# Sheet1.net
KiCad netlist of a schematic drawn in Altium Designer
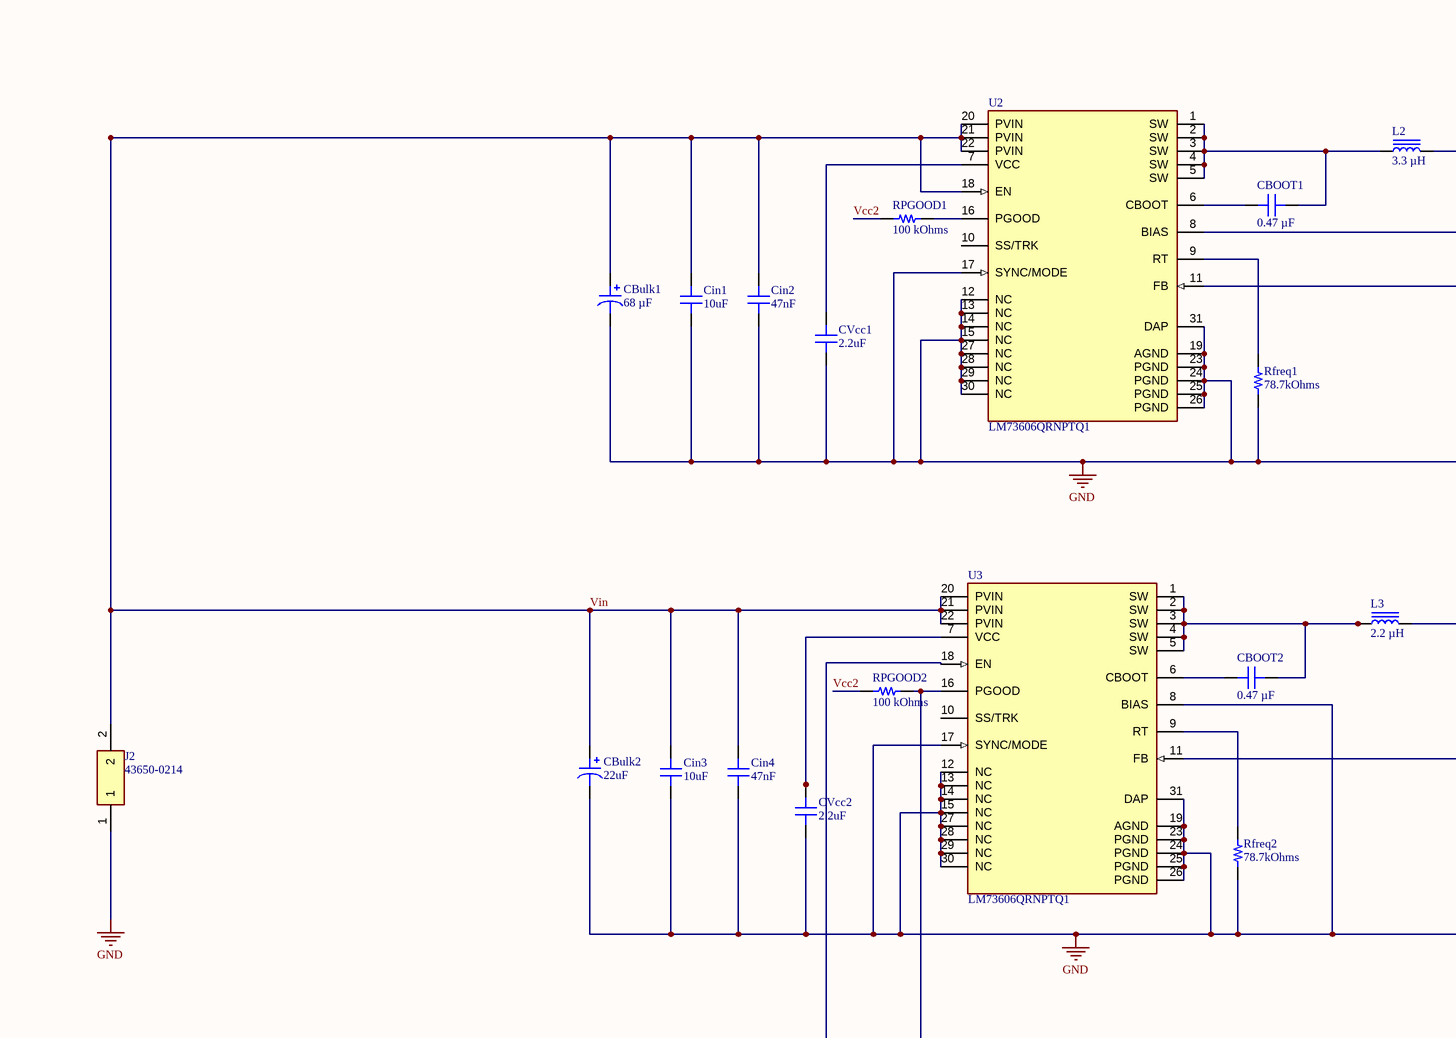
[diagram p0: Sheet1.SchDoc, top left]
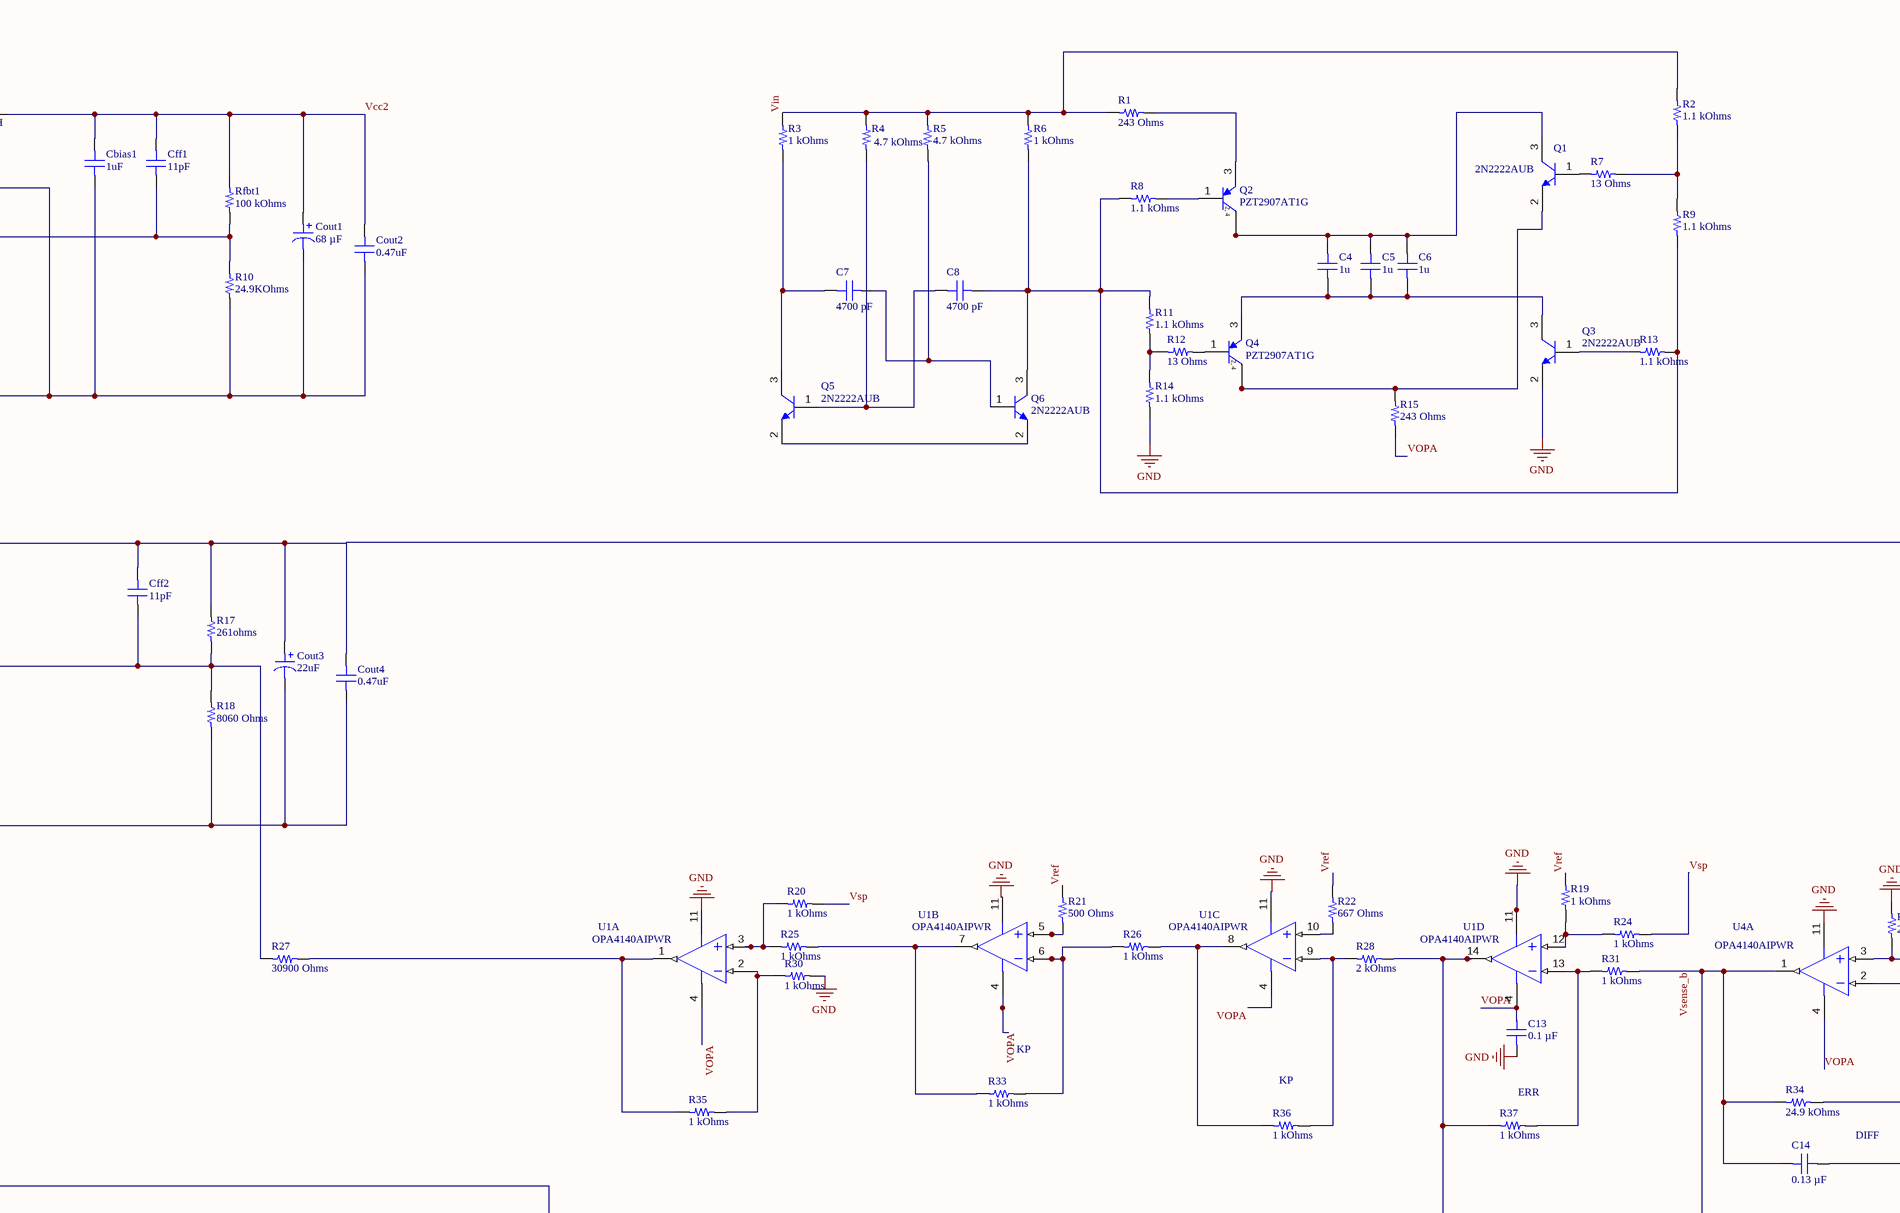
[diagram p1: Sheet1.SchDoc, top middle]
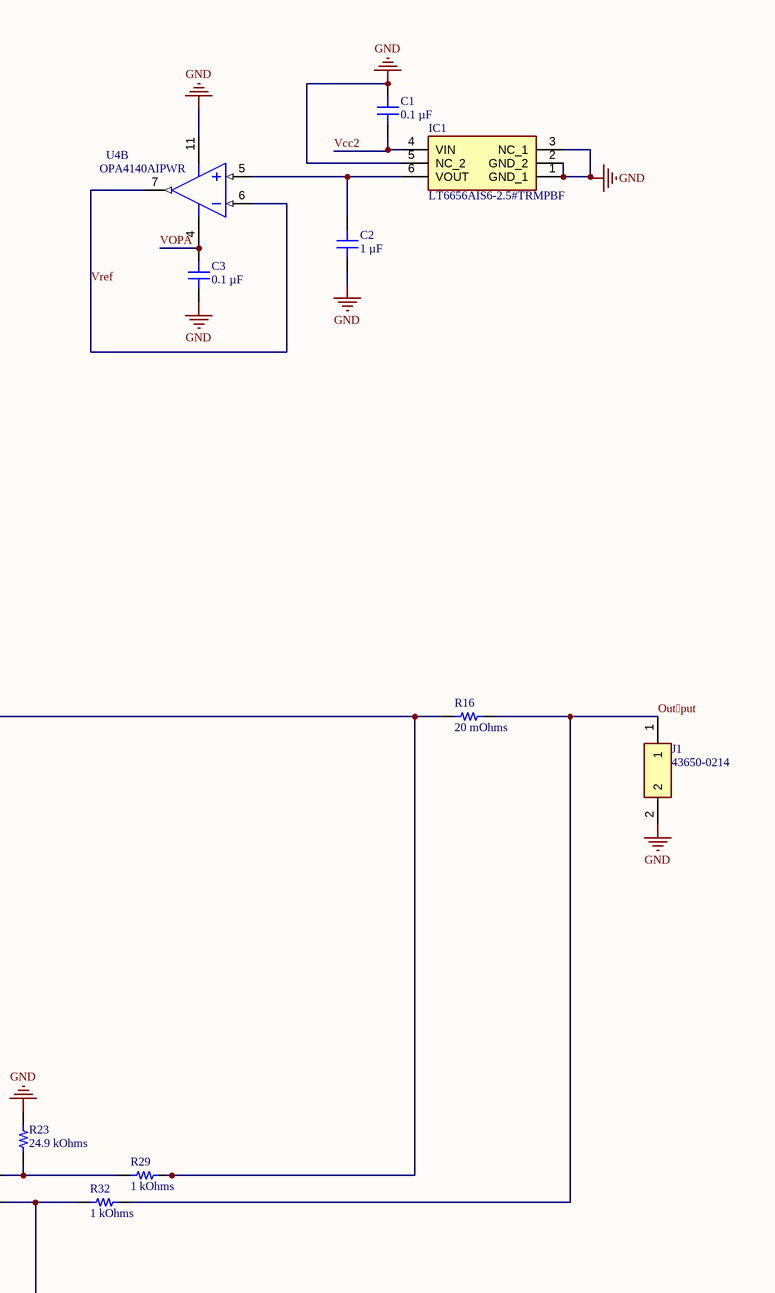
[diagram p2: Sheet1.SchDoc, top right]
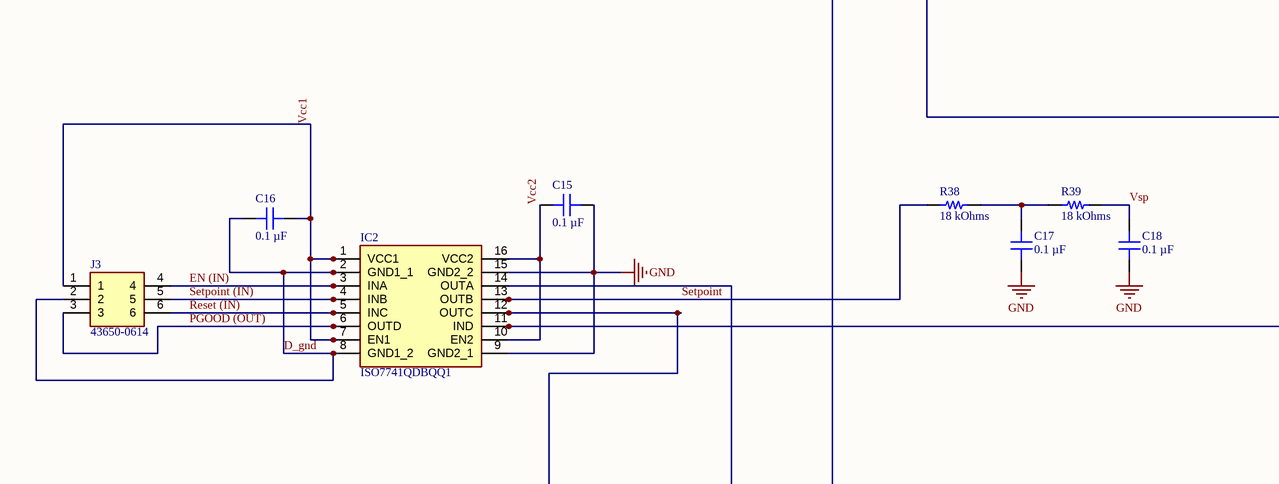
[diagram p3: Sheet1.SchDoc, bottom left]
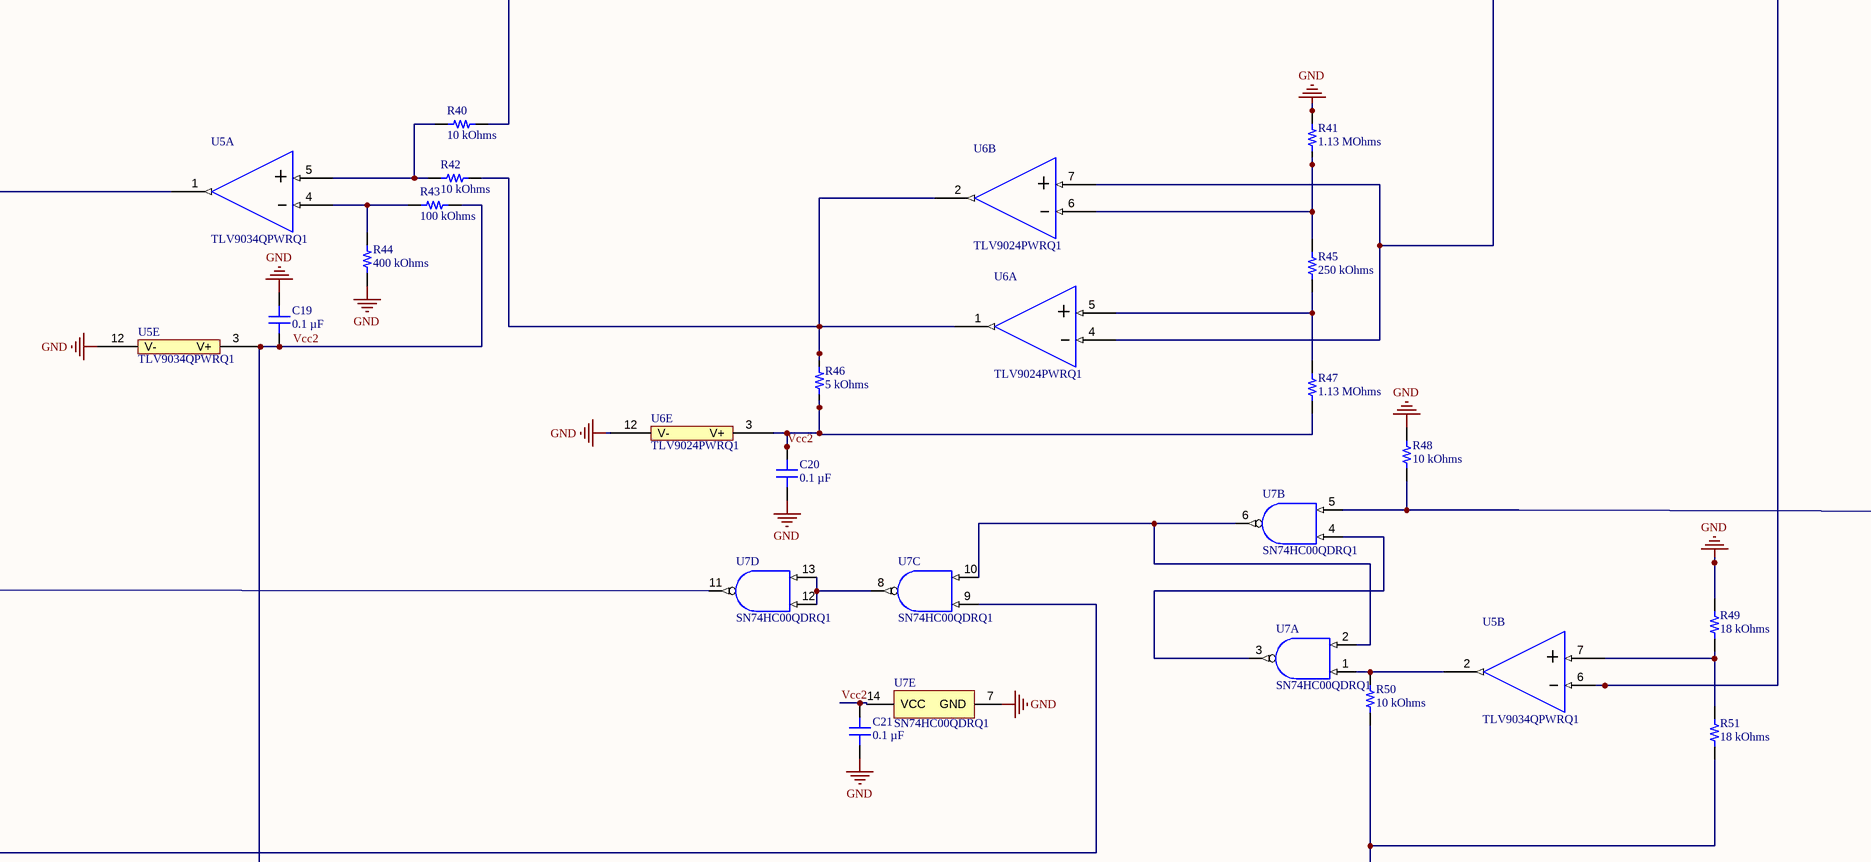
[diagram p4: Sheet1.SchDoc, bottom middle]

(export (version "E")
  (design (tool "Eeschema 10.0.6"))
  (components
    (comp (ref "C1")
      (value "0.1 µF")
      (footprint "CAP 0805_2012")
      (description "CAP CER 0.1UF 50V X7R 0805")
      (fields (field (name "PART NUMBER") "CC0805MRX7R9BB104") (field (name "MANUFACTURER") "Yageo"))
      (libsource (lib "Celestial Altium Library - altium_library") (part "Capacitor"))
    )
    (comp (ref "C2")
      (value "1 µF")
      (footprint "CAP 0805_2012")
      (description "CAP CER 0.1UF 50V X7R 0805")
      (fields (field (name "PART NUMBER") "CC0805MRX7R9BB104") (field (name "MANUFACTURER") "Yageo"))
      (libsource (lib "Celestial Altium Library - altium_library") (part "Capacitor"))
    )
    (comp (ref "C3")
      (value "0.1 µF")
      (footprint "CAP 0805_2012")
      (description "CAP CER 0.1UF 50V X7R 0805")
      (fields (field (name "PART NUMBER") "CC0805MRX7R9BB104") (field (name "MANUFACTURER") "Yageo"))
      (libsource (lib "Celestial Altium Library - altium_library") (part "Capacitor"))
    )
    (comp (ref "C4")
      (value "1u")
      (footprint "CAP 0805_2012")
      (description "CAP CER 0805 4.7NF 25V C0G 1%")
      (fields (field (name "PART NUMBER") "C0805C472F3GECAUTO7210") (field (name "MANUFACTURER") "KEMET"))
      (libsource (lib "Celestial Altium Library - altium_library") (part "Capacitor"))
    )
    (comp (ref "C5")
      (value "1u")
      (footprint "CAP 0805_2012")
      (description "CAP CER 0805 4.7NF 25V C0G 1%")
      (fields (field (name "PART NUMBER") "C0805C472F3GECAUTO7210") (field (name "MANUFACTURER") "KEMET"))
      (libsource (lib "Celestial Altium Library - altium_library") (part "Capacitor"))
    )
    (comp (ref "C6")
      (value "1u")
      (footprint "CAP 0805_2012")
      (description "CAP CER 0805 4.7NF 25V C0G 1%")
      (fields (field (name "PART NUMBER") "C0805C472F3GECAUTO7210") (field (name "MANUFACTURER") "KEMET"))
      (libsource (lib "Celestial Altium Library - altium_library") (part "Capacitor"))
    )
    (comp (ref "C7")
      (value "4700 pF")
      (footprint "CAP 0805_2012")
      (description "CAP CER 0805 4.7NF 25V C0G 1%")
      (fields (field (name "PART NUMBER") "C0805C472F3GECAUTO7210") (field (name "MANUFACTURER") "KEMET"))
      (libsource (lib "Celestial Altium Library - altium_library") (part "Capacitor"))
    )
    (comp (ref "C8")
      (value "4700 pF")
      (footprint "CAP 0805_2012")
      (description "CAP CER 0805 4.7NF 25V C0G 1%")
      (fields (field (name "PART NUMBER") "C0805C472F3GECAUTO7210") (field (name "MANUFACTURER") "KEMET"))
      (libsource (lib "Celestial Altium Library - altium_library") (part "Capacitor"))
    )
    (comp (ref "C13")
      (value "0.1 µF")
      (footprint "CAP 0805_2012")
      (description "CAP CER 0.1UF 50V X7R 0805")
      (fields (field (name "PART NUMBER") "CC0805MRX7R9BB104") (field (name "MANUFACTURER") "Yageo"))
      (libsource (lib "Celestial Altium Library - altium_library") (part "Capacitor"))
    )
    (comp (ref "C14")
      (value "0.13 µF")
      (footprint "CAP 0805_2012")
      (description "CAP CER 0.1UF 50V X7R 0805")
      (fields (field (name "PART NUMBER") "CC0805MRX7R9BB104") (field (name "MANUFACTURER") "Yageo"))
      (libsource (lib "Celestial Altium Library - altium_library") (part "Capacitor"))
    )
    (comp (ref "C15")
      (value "0.1 µF")
      (footprint "CAP 0805_2012")
      (description "CAP CER 0.1UF 25V X7R 0805")
      (fields
        (field (name "PART NUMBER") "250X15W104MV4E")
        (field (name "MANUFACTURER") "Johanson Dielectrics Inc.")
      )
      (libsource (lib "Celestial Altium Library - altium_library") (part "Capacitor"))
    )
    (comp (ref "C16")
      (value "0.1 µF")
      (footprint "CAP 0805_2012")
      (description "CAP CER 0.1UF 25V X7R 0805")
      (fields
        (field (name "PART NUMBER") "250X15W104MV4E")
        (field (name "MANUFACTURER") "Johanson Dielectrics Inc.")
      )
      (libsource (lib "Celestial Altium Library - altium_library") (part "Capacitor"))
    )
    (comp (ref "C17")
      (value "0.1 µF")
      (footprint "CAP 0805_2012")
      (description "CAP CER 0.1UF 25V X7R 0805")
      (fields
        (field (name "PART NUMBER") "250X15W104MV4E")
        (field (name "MANUFACTURER") "Johanson Dielectrics Inc.")
      )
      (libsource (lib "Celestial Altium Library - altium_library") (part "Capacitor"))
    )
    (comp (ref "C18")
      (value "0.1 µF")
      (footprint "CAP 0805_2012")
      (description "CAP CER 0.1UF 25V X7R 0805")
      (fields
        (field (name "PART NUMBER") "250X15W104MV4E")
        (field (name "MANUFACTURER") "Johanson Dielectrics Inc.")
      )
      (libsource (lib "Celestial Altium Library - altium_library") (part "Capacitor"))
    )
    (comp (ref "C19")
      (value "0.1 µF")
      (footprint "CAP 0805_2012")
      (description "CAP CER 0.1UF 25V X7R 0805")
      (fields
        (field (name "PART NUMBER") "250X15W104MV4E")
        (field (name "MANUFACTURER") "Johanson Dielectrics Inc.")
      )
      (libsource (lib "Celestial Altium Library - altium_library") (part "Capacitor"))
    )
    (comp (ref "C20")
      (value "0.1 µF")
      (footprint "CAP 0805_2012")
      (description "CAP CER 0.1UF 25V X7R 0805")
      (fields
        (field (name "PART NUMBER") "250X15W104MV4E")
        (field (name "MANUFACTURER") "Johanson Dielectrics Inc.")
      )
      (libsource (lib "Celestial Altium Library - altium_library") (part "Capacitor"))
    )
    (comp (ref "C21")
      (value "0.1 µF")
      (footprint "CAP 0805_2012")
      (description "CAP CER 0.1UF 25V X7R 0805")
      (fields
        (field (name "PART NUMBER") "250X15W104MV4E")
        (field (name "MANUFACTURER") "Johanson Dielectrics Inc.")
      )
      (libsource (lib "Celestial Altium Library - altium_library") (part "Capacitor"))
    )
    (comp (ref "Cbias1")
      (value "1uF")
      (footprint "CAP 0805_2012")
      (description "CAP CER 0.1UF 25V X7R 0805")
      (fields
        (field (name "PART NUMBER") "250X15W104MV4E")
        (field (name "MANUFACTURER") "Johanson Dielectrics Inc.")
      )
      (libsource (lib "Celestial Altium Library - altium_library") (part "Capacitor"))
    )
    (comp (ref "CBOOT1")
      (value "0.47 µF")
      (footprint "CAP 0805_2012")
      (description "CAP CER 0.1UF 25V X7R 0805")
      (fields
        (field (name "PART NUMBER") "250X15W104MV4E")
        (field (name "MANUFACTURER") "Johanson Dielectrics Inc.")
      )
      (libsource (lib "Celestial Altium Library - altium_library") (part "Capacitor"))
    )
    (comp (ref "CBOOT2")
      (value "0.47 µF")
      (footprint "CAP 0805_2012")
      (description "CAP CER 0.1UF 25V X7R 0805")
      (fields
        (field (name "PART NUMBER") "250X15W104MV4E")
        (field (name "MANUFACTURER") "Johanson Dielectrics Inc.")
      )
      (libsource (lib "Celestial Altium Library - altium_library") (part "Capacitor"))
    )
    (comp (ref "CBulk1")
      (value "68 µF")
      (footprint "CAP ALSMD 8.3MM H10.5MM")
      (description "CAP ALUM 68UF 20% 63V SMD")
      (fields
        (field (name "PART NUMBER") "EEE-FK1J680UP")
        (field (name "MANUFACTURER") "Panasonic Electronic Components")
      )
      (libsource (lib "Celestial Altium Library - altium_library") (part "Polarised Capacitor"))
    )
    (comp (ref "CBulk2")
      (value "22uF")
      (footprint "CAP ALSMD 8.3MM H10.5MM")
      (description "CAP ALUM 68UF 20% 63V SMD")
      (fields
        (field (name "PART NUMBER") "EEE-FK1J680UP")
        (field (name "MANUFACTURER") "Panasonic Electronic Components")
      )
      (libsource (lib "Celestial Altium Library - altium_library") (part "Polarised Capacitor"))
    )
    (comp (ref "Cff1")
      (value "11pF")
      (footprint "CAP 0805_2012")
      (description "CAP CER 0.1UF 25V X7R 0805")
      (fields
        (field (name "PART NUMBER") "250X15W104MV4E")
        (field (name "MANUFACTURER") "Johanson Dielectrics Inc.")
      )
      (libsource (lib "Celestial Altium Library - altium_library") (part "Capacitor"))
    )
    (comp (ref "Cff2")
      (value "11pF")
      (footprint "CAP 0805_2012")
      (description "CAP CER 0.1UF 25V X7R 0805")
      (fields
        (field (name "PART NUMBER") "250X15W104MV4E")
        (field (name "MANUFACTURER") "Johanson Dielectrics Inc.")
      )
      (libsource (lib "Celestial Altium Library - altium_library") (part "Capacitor"))
    )
    (comp (ref "Cin1")
      (value "10uF")
      (footprint "CAP 0805_2012")
      (description "CAP CER 0.1UF 25V X7R 0805")
      (fields
        (field (name "PART NUMBER") "250X15W104MV4E")
        (field (name "MANUFACTURER") "Johanson Dielectrics Inc.")
      )
      (libsource (lib "Celestial Altium Library - altium_library") (part "Capacitor"))
    )
    (comp (ref "Cin2")
      (value "47nF")
      (footprint "CAP 0805_2012")
      (description "CAP CER 0.1UF 25V X7R 0805")
      (fields
        (field (name "PART NUMBER") "250X15W104MV4E")
        (field (name "MANUFACTURER") "Johanson Dielectrics Inc.")
      )
      (libsource (lib "Celestial Altium Library - altium_library") (part "Capacitor"))
    )
    (comp (ref "Cin3")
      (value "10uF")
      (footprint "CAP 0805_2012")
      (description "CAP CER 0.1UF 25V X7R 0805")
      (fields
        (field (name "PART NUMBER") "250X15W104MV4E")
        (field (name "MANUFACTURER") "Johanson Dielectrics Inc.")
      )
      (libsource (lib "Celestial Altium Library - altium_library") (part "Capacitor"))
    )
    (comp (ref "Cin4")
      (value "47nF")
      (footprint "CAP 0805_2012")
      (description "CAP CER 0.1UF 25V X7R 0805")
      (fields
        (field (name "PART NUMBER") "250X15W104MV4E")
        (field (name "MANUFACTURER") "Johanson Dielectrics Inc.")
      )
      (libsource (lib "Celestial Altium Library - altium_library") (part "Capacitor"))
    )
    (comp (ref "Cout1")
      (value "68 µF")
      (footprint "CAP ALSMD 8.3MM H10.5MM")
      (description "CAP ALUM 68UF 20% 63V SMD")
      (fields
        (field (name "PART NUMBER") "EEE-FK1J680UP")
        (field (name "MANUFACTURER") "Panasonic Electronic Components")
      )
      (libsource (lib "Celestial Altium Library - altium_library") (part "Polarised Capacitor"))
    )
    (comp (ref "Cout2")
      (value "0.47uF")
      (footprint "CAP 0805_2012")
      (description "CAP CER 0.1UF 25V X7R 0805")
      (fields
        (field (name "PART NUMBER") "250X15W104MV4E")
        (field (name "MANUFACTURER") "Johanson Dielectrics Inc.")
      )
      (libsource (lib "Celestial Altium Library - altium_library") (part "Capacitor"))
    )
    (comp (ref "Cout3")
      (value "22uF")
      (footprint "CAP ALSMD 8.3MM H10.5MM")
      (description "CAP ALUM 68UF 20% 63V SMD")
      (fields
        (field (name "PART NUMBER") "EEE-FK1J680UP")
        (field (name "MANUFACTURER") "Panasonic Electronic Components")
      )
      (libsource (lib "Celestial Altium Library - altium_library") (part "Polarised Capacitor"))
    )
    (comp (ref "Cout4")
      (value "0.47uF")
      (footprint "CAP 0805_2012")
      (description "CAP CER 0.1UF 25V X7R 0805")
      (fields
        (field (name "PART NUMBER") "250X15W104MV4E")
        (field (name "MANUFACTURER") "Johanson Dielectrics Inc.")
      )
      (libsource (lib "Celestial Altium Library - altium_library") (part "Capacitor"))
    )
    (comp (ref "CVcc1")
      (value "2.2uF")
      (footprint "CAP 0805_2012")
      (description "CAP CER 0.1UF 25V X7R 0805")
      (fields
        (field (name "PART NUMBER") "250X15W104MV4E")
        (field (name "MANUFACTURER") "Johanson Dielectrics Inc.")
      )
      (libsource (lib "Celestial Altium Library - altium_library") (part "Capacitor"))
    )
    (comp (ref "CVcc2")
      (value "2.2uF")
      (footprint "CAP 0805_2012")
      (description "CAP CER 0.1UF 25V X7R 0805")
      (fields
        (field (name "PART NUMBER") "250X15W104MV4E")
        (field (name "MANUFACTURER") "Johanson Dielectrics Inc.")
      )
      (libsource (lib "Celestial Altium Library - altium_library") (part "Capacitor"))
    )
    (comp (ref "IC1")
      (value "LT6656AIS6-2.5#TRMPBF")
      (footprint "SOT95P280X100-6N")
      (description "Integrated Circuit")
      (fields (field (name "MOUSER PART NUMBER") "584-6656AIS6-2.5TMPF"))
      (libsource (lib "*") (part "LT6656AIS6-2.5#TRMPBF"))
    )
    (comp (ref "IC2")
      (value "ISO7741QDBQQ1")
      (footprint "SOP64P600X175-16N")
      (description "Integrated Circuit")
      (fields (field (name "MOUSER PART NUMBER") "595-ISO7741QDBQQ1"))
      (libsource (lib "SamacSys") (part "ISO7741QDBQQ1"))
    )
    (comp (ref "J1")
      (value "43650-0214")
      (footprint "43650-02(12,13,14)")
      (description "Connector")
      (fields (field (name "MOUSER PART NUMBER") "538-43650-0214"))
      (libsource (lib "") (part "43650-0214_1"))
    )
    (comp (ref "J2")
      (value "43650-0214")
      (footprint "43650-02(12,13,14)")
      (description "Connector")
      (fields (field (name "MOUSER PART NUMBER") "538-43650-0214"))
      (libsource (lib "*") (part "43650-0214"))
    )
    (comp (ref "J3")
      (value "43650-0614")
      (footprint "43650-06(12,13,14)")
      (description "Connector")
      (fields (field (name "MOUSER PART NUMBER") "538-43650-0614"))
      (libsource (lib "*") (part "43650-0614"))
    )
    (comp (ref "L2")
      (value "3.3 µH")
      (footprint "BOURNS SRR1280")
      (description "FIXED IND 3.3UH 8.8A 12 MOHM SMD")
      (fields (field (name "PART NUMBER") "SRR1280-3R3Y") (field (name "MANUFACTURER") "Bourns Inc."))
      (libsource (lib "Celestial Altium Library - altium_library") (part "Inductor"))
    )
    (comp (ref "L3")
      (value "2.2 µH")
      (footprint "WURTH WE-PD 1210")
      (description "FIXED IND 2.2UH 11.5A 6 MOHM SMD")
      (fields (field (name "PART NUMBER") "7447709002") (field (name "MANUFACTURER") "Würth Elektronik"))
      (libsource (lib "Celestial Altium Library - altium_library") (part "Inductor"))
    )
    (comp (ref "Q1")
      (value "2N2222AUB")
      (footprint "MCSM-2N2222AUB-3")
      (description "NPN Transistor, 50 V, 0.8 A, -65 to 200 degC, 3-Pin SMD, Tray")
      (fields (field (name "MANUFACTURER") "Microsemi"))
      (libsource (lib "Altium Content Vault") (part "BJT-NPN-BEC-3"))
    )
    (comp (ref "Q2")
      (value "PZT2907AT1G")
      (footprint "ONSC-SOT-223-4-318E-04_V")
      (description "PNP Silicon Epitaxial Transistor, 4-Pin SOT-223, Pb-Free, Tape and Reel")
      (fields (field (name "MANUFACTURER") "On Semiconductor"))
      (libsource (lib "Altium Content Vault") (part "ONSC-PNP-B1C2E3C4-4"))
    )
    (comp (ref "Q3")
      (value "2N2222AUB")
      (footprint "MCSM-2N2222AUB-3")
      (description "NPN Transistor, 50 V, 0.8 A, -65 to 200 degC, 3-Pin SMD, Tray")
      (fields (field (name "MANUFACTURER") "Microsemi"))
      (libsource (lib "Altium Content Vault") (part "BJT-NPN-BEC-3"))
    )
    (comp (ref "Q4")
      (value "PZT2907AT1G")
      (footprint "ONSC-SOT-223-4-318E-04_V")
      (description "PNP Silicon Epitaxial Transistor, 4-Pin SOT-223, Pb-Free, Tape and Reel")
      (fields (field (name "MANUFACTURER") "On Semiconductor"))
      (libsource (lib "Altium Content Vault") (part "ONSC-PNP-B1C2E3C4-4"))
    )
    (comp (ref "Q5")
      (value "2N2222AUB")
      (footprint "MCSM-2N2222AUB-3")
      (description "NPN Transistor, 50 V, 0.8 A, -65 to 200 degC, 3-Pin SMD, Tray")
      (fields (field (name "MANUFACTURER") "Microsemi"))
      (libsource (lib "Altium Content Vault") (part "BJT-NPN-BEC-3"))
    )
    (comp (ref "Q6")
      (value "2N2222AUB")
      (footprint "MCSM-2N2222AUB-3")
      (description "NPN Transistor, 50 V, 0.8 A, -65 to 200 degC, 3-Pin SMD, Tray")
      (fields (field (name "MANUFACTURER") "Microsemi"))
      (libsource (lib "Altium Content Vault") (part "BJT-NPN-BEC-3"))
    )
    (comp (ref "R1")
      (value "243 Ohms")
      (footprint "RES 0805_2012")
      (description "RES SMD 4.7K OHM 1% 1/8W 0805")
      (fields (field (name "PART NUMBER") "AC0805FR-074K7L") (field (name "MANUFACTURER") "Yageo"))
      (libsource (lib "Celestial Altium Library - altium_library") (part "Resistor"))
    )
    (comp (ref "R2")
      (value "1.1 kOhms")
      (footprint "RES 0805_2012")
      (description "RES SMD 4.7K OHM 1% 1/8W 0805")
      (fields (field (name "PART NUMBER") "AC0805FR-074K7L") (field (name "MANUFACTURER") "Yageo"))
      (libsource (lib "Celestial Altium Library - altium_library") (part "Resistor"))
    )
    (comp (ref "R3")
      (value "1 kOhms")
      (footprint "RES 0805_2012")
      (description "RES SMD 4.7K OHM 1% 1/8W 0805")
      (fields (field (name "PART NUMBER") "AC0805FR-074K7L") (field (name "MANUFACTURER") "Yageo"))
      (libsource (lib "Celestial Altium Library - altium_library") (part "Resistor"))
    )
    (comp (ref "R4")
      (value "4.7 kOhms")
      (footprint "RES 0805_2012")
      (description "RES SMD 4.7K OHM 1% 1/8W 0805")
      (fields (field (name "PART NUMBER") "AC0805FR-074K7L") (field (name "MANUFACTURER") "Yageo"))
      (libsource (lib "Celestial Altium Library - altium_library") (part "Resistor"))
    )
    (comp (ref "R5")
      (value "4.7 kOhms")
      (footprint "RES 0805_2012")
      (description "RES SMD 4.7K OHM 1% 1/8W 0805")
      (fields (field (name "PART NUMBER") "AC0805FR-074K7L") (field (name "MANUFACTURER") "Yageo"))
      (libsource (lib "Celestial Altium Library - altium_library") (part "Resistor"))
    )
    (comp (ref "R6")
      (value "1 kOhms")
      (footprint "RES 0805_2012")
      (description "RES SMD 4.7K OHM 1% 1/8W 0805")
      (fields (field (name "PART NUMBER") "AC0805FR-074K7L") (field (name "MANUFACTURER") "Yageo"))
      (libsource (lib "Celestial Altium Library - altium_library") (part "Resistor"))
    )
    (comp (ref "R7")
      (value "13 Ohms")
      (footprint "RES 0805_2012")
      (description "RES SMD 4.7K OHM 1% 1/8W 0805")
      (fields (field (name "PART NUMBER") "AC0805FR-074K7L") (field (name "MANUFACTURER") "Yageo"))
      (libsource (lib "Celestial Altium Library - altium_library") (part "Resistor"))
    )
    (comp (ref "R8")
      (value "1.1 kOhms")
      (footprint "RES 0805_2012")
      (description "RES SMD 4.7K OHM 1% 1/8W 0805")
      (fields (field (name "PART NUMBER") "AC0805FR-074K7L") (field (name "MANUFACTURER") "Yageo"))
      (libsource (lib "Celestial Altium Library - altium_library") (part "Resistor"))
    )
    (comp (ref "R9")
      (value "1.1 kOhms")
      (footprint "RES 0805_2012")
      (description "RES SMD 4.7K OHM 1% 1/8W 0805")
      (fields (field (name "PART NUMBER") "AC0805FR-074K7L") (field (name "MANUFACTURER") "Yageo"))
      (libsource (lib "Celestial Altium Library - altium_library") (part "Resistor"))
    )
    (comp (ref "R10")
      (value "24.9KOhms")
      (footprint "RES 0805_2012")
      (description "RES SMD 1K OHM 0.1% 1/4W 0805")
      (fields
        (field (name "PART NUMBER") "1-2176092-8")
        (field (name "MANUFACTURER") "TE Connectivity Passive Product")
      )
      (libsource (lib "Celestial Altium Library - altium_library") (part "Resistor"))
    )
    (comp (ref "R11")
      (value "1.1 kOhms")
      (footprint "RES 0805_2012")
      (description "RES SMD 4.7K OHM 1% 1/8W 0805")
      (fields (field (name "PART NUMBER") "AC0805FR-074K7L") (field (name "MANUFACTURER") "Yageo"))
      (libsource (lib "Celestial Altium Library - altium_library") (part "Resistor"))
    )
    (comp (ref "R12")
      (value "13 Ohms")
      (footprint "RES 0805_2012")
      (description "RES SMD 4.7K OHM 1% 1/8W 0805")
      (fields (field (name "PART NUMBER") "AC0805FR-074K7L") (field (name "MANUFACTURER") "Yageo"))
      (libsource (lib "Celestial Altium Library - altium_library") (part "Resistor"))
    )
    (comp (ref "R13")
      (value "1.1 kOhms")
      (footprint "RES 0805_2012")
      (description "RES SMD 4.7K OHM 1% 1/8W 0805")
      (fields (field (name "PART NUMBER") "AC0805FR-074K7L") (field (name "MANUFACTURER") "Yageo"))
      (libsource (lib "Celestial Altium Library - altium_library") (part "Resistor"))
    )
    (comp (ref "R14")
      (value "1.1 kOhms")
      (footprint "RES 0805_2012")
      (description "RES SMD 4.7K OHM 1% 1/8W 0805")
      (fields (field (name "PART NUMBER") "AC0805FR-074K7L") (field (name "MANUFACTURER") "Yageo"))
      (libsource (lib "Celestial Altium Library - altium_library") (part "Resistor"))
    )
    (comp (ref "R15")
      (value "243 Ohms")
      (footprint "RES 0805_2012")
      (description "RES SMD 4.7K OHM 1% 1/8W 0805")
      (fields (field (name "PART NUMBER") "AC0805FR-074K7L") (field (name "MANUFACTURER") "Yageo"))
      (libsource (lib "Celestial Altium Library - altium_library") (part "Resistor"))
    )
    (comp (ref "R16")
      (value "20 mOhms")
      (footprint "RES 0805_2012")
      (description "RES 0.02 OHM 1% 3/4W 0805")
      (fields (field (name "PART NUMBER") "CFN0805-FX-R020ELF") (field (name "MANUFACTURER") "Bourns Inc."))
      (libsource (lib "Celestial Altium Library - altium_library") (part "Resistor"))
    )
    (comp (ref "R17")
      (value "261ohms")
      (footprint "RES 0805_2012")
      (description "RES SMD 1K OHM 0.1% 1/4W 0805")
      (fields
        (field (name "PART NUMBER") "1-2176092-8")
        (field (name "MANUFACTURER") "TE Connectivity Passive Product")
      )
      (libsource (lib "Celestial Altium Library - altium_library") (part "Resistor"))
    )
    (comp (ref "R18")
      (value "8060 Ohms")
      (footprint "RES 0805_2012")
      (description "RES SMD 1K OHM 0.1% 1/4W 0805")
      (fields
        (field (name "PART NUMBER") "1-2176092-8")
        (field (name "MANUFACTURER") "TE Connectivity Passive Product")
      )
      (libsource (lib "Celestial Altium Library - altium_library") (part "Resistor"))
    )
    (comp (ref "R19")
      (value "1 kOhms")
      (footprint "RES 0805_2012")
      (description "RES SMD 1K OHM 0.1% 1/4W 0805")
      (fields
        (field (name "PART NUMBER") "1-2176092-8")
        (field (name "MANUFACTURER") "TE Connectivity Passive Product")
      )
      (libsource (lib "Celestial Altium Library - altium_library") (part "Resistor"))
    )
    (comp (ref "R20")
      (value "1 kOhms")
      (footprint "RES 0805_2012")
      (description "RES SMD 1K OHM 0.1% 1/4W 0805")
      (fields
        (field (name "PART NUMBER") "1-2176092-8")
        (field (name "MANUFACTURER") "TE Connectivity Passive Product")
      )
      (libsource (lib "Celestial Altium Library - altium_library") (part "Resistor"))
    )
    (comp (ref "R21")
      (value "500 Ohms")
      (footprint "RES 0805_2012")
      (description "RES SMD 1K OHM 0.1% 1/4W 0805")
      (fields
        (field (name "PART NUMBER") "1-2176092-8")
        (field (name "MANUFACTURER") "TE Connectivity Passive Product")
      )
      (libsource (lib "Celestial Altium Library - altium_library") (part "Resistor"))
    )
    (comp (ref "R22")
      (value "667 Ohms")
      (footprint "RES 0805_2012")
      (description "RES SMD 1K OHM 0.1% 1/4W 0805")
      (fields
        (field (name "PART NUMBER") "1-2176092-8")
        (field (name "MANUFACTURER") "TE Connectivity Passive Product")
      )
      (libsource (lib "Celestial Altium Library - altium_library") (part "Resistor"))
    )
    (comp (ref "R23")
      (value "24.9 kOhms")
      (footprint "RES 0805_2012")
      (description "RES SMD 71.5 OHM 0.1% 1/4W 0805")
      (fields
        (field (name "PART NUMBER") "1-2176091-0")
        (field (name "MANUFACTURER") "TE Connectivity Passive Product")
      )
      (libsource (lib "Celestial Altium Library - altium_library") (part "Resistor"))
    )
    (comp (ref "R24")
      (value "1 kOhms")
      (footprint "RES 0805_2012")
      (description "RES SMD 1K OHM 0.1% 1/4W 0805")
      (fields
        (field (name "PART NUMBER") "1-2176092-8")
        (field (name "MANUFACTURER") "TE Connectivity Passive Product")
      )
      (libsource (lib "Celestial Altium Library - altium_library") (part "Resistor"))
    )
    (comp (ref "R25")
      (value "1 kOhms")
      (footprint "RES 0805_2012")
      (description "RES SMD 1K OHM 0.1% 1/4W 0805")
      (fields
        (field (name "PART NUMBER") "1-2176092-8")
        (field (name "MANUFACTURER") "TE Connectivity Passive Product")
      )
      (libsource (lib "Celestial Altium Library - altium_library") (part "Resistor"))
    )
    (comp (ref "R26")
      (value "1 kOhms")
      (footprint "RES 0805_2012")
      (description "RES SMD 1K OHM 0.1% 1/4W 0805")
      (fields
        (field (name "PART NUMBER") "1-2176092-8")
        (field (name "MANUFACTURER") "TE Connectivity Passive Product")
      )
      (libsource (lib "Celestial Altium Library - altium_library") (part "Resistor"))
    )
    (comp (ref "R27")
      (value "30900 Ohms")
      (footprint "RES 0805_2012")
      (description "RES SMD 1K OHM 0.1% 1/4W 0805")
      (fields
        (field (name "PART NUMBER") "1-2176092-8")
        (field (name "MANUFACTURER") "TE Connectivity Passive Product")
      )
      (libsource (lib "Celestial Altium Library - altium_library") (part "Resistor"))
    )
    (comp (ref "R28")
      (value "2 kOhms")
      (footprint "RES 0805_2012")
      (description "RES SMD 1K OHM 0.1% 1/4W 0805")
      (fields
        (field (name "PART NUMBER") "1-2176092-8")
        (field (name "MANUFACTURER") "TE Connectivity Passive Product")
      )
      (libsource (lib "Celestial Altium Library - altium_library") (part "Resistor"))
    )
    (comp (ref "R29")
      (value "1 kOhms")
      (footprint "RES 0805_2012")
      (description "RES SMD 1K OHM 0.1% 1/4W 0805")
      (fields
        (field (name "PART NUMBER") "1-2176092-8")
        (field (name "MANUFACTURER") "TE Connectivity Passive Product")
      )
      (libsource (lib "Celestial Altium Library - altium_library") (part "Resistor"))
    )
    (comp (ref "R30")
      (value "1 kOhms")
      (footprint "RES 0805_2012")
      (description "RES SMD 1K OHM 0.1% 1/4W 0805")
      (fields
        (field (name "PART NUMBER") "1-2176092-8")
        (field (name "MANUFACTURER") "TE Connectivity Passive Product")
      )
      (libsource (lib "Celestial Altium Library - altium_library") (part "Resistor"))
    )
    (comp (ref "R31")
      (value "1 kOhms")
      (footprint "RES 0805_2012")
      (description "RES SMD 1K OHM 0.1% 1/4W 0805")
      (fields
        (field (name "PART NUMBER") "1-2176092-8")
        (field (name "MANUFACTURER") "TE Connectivity Passive Product")
      )
      (libsource (lib "Celestial Altium Library - altium_library") (part "Resistor"))
    )
    (comp (ref "R32")
      (value "1 kOhms")
      (footprint "RES 0805_2012")
      (description "RES SMD 1K OHM 0.1% 1/4W 0805")
      (fields
        (field (name "PART NUMBER") "1-2176092-8")
        (field (name "MANUFACTURER") "TE Connectivity Passive Product")
      )
      (libsource (lib "Celestial Altium Library - altium_library") (part "Resistor"))
    )
    (comp (ref "R33")
      (value "1 kOhms")
      (footprint "RES 0805_2012")
      (description "RES SMD 1K OHM 0.1% 1/4W 0805")
      (fields
        (field (name "PART NUMBER") "1-2176092-8")
        (field (name "MANUFACTURER") "TE Connectivity Passive Product")
      )
      (libsource (lib "Celestial Altium Library - altium_library") (part "Resistor"))
    )
    (comp (ref "R34")
      (value "24.9 kOhms")
      (footprint "RES 0805_2012")
      (description "RES SMD 71.5 OHM 0.1% 1/4W 0805")
      (fields
        (field (name "PART NUMBER") "1-2176091-0")
        (field (name "MANUFACTURER") "TE Connectivity Passive Product")
      )
      (libsource (lib "Celestial Altium Library - altium_library") (part "Resistor"))
    )
    (comp (ref "R35")
      (value "1 kOhms")
      (footprint "RES 0805_2012")
      (description "RES SMD 1K OHM 0.1% 1/4W 0805")
      (fields
        (field (name "PART NUMBER") "1-2176092-8")
        (field (name "MANUFACTURER") "TE Connectivity Passive Product")
      )
      (libsource (lib "Celestial Altium Library - altium_library") (part "Resistor"))
    )
    (comp (ref "R36")
      (value "1 kOhms")
      (footprint "RES 0805_2012")
      (description "RES SMD 1K OHM 0.1% 1/4W 0805")
      (fields
        (field (name "PART NUMBER") "1-2176092-8")
        (field (name "MANUFACTURER") "TE Connectivity Passive Product")
      )
      (libsource (lib "Celestial Altium Library - altium_library") (part "Resistor"))
    )
    (comp (ref "R37")
      (value "1 kOhms")
      (footprint "RES 0805_2012")
      (description "RES SMD 1K OHM 0.1% 1/4W 0805")
      (fields
        (field (name "PART NUMBER") "1-2176092-8")
        (field (name "MANUFACTURER") "TE Connectivity Passive Product")
      )
      (libsource (lib "Celestial Altium Library - altium_library") (part "Resistor"))
    )
    (comp (ref "R38")
      (value "18 kOhms")
      (footprint "RES 0805_2012")
      (description "RES SMD 1K OHM 0.1% 1/4W 0805")
      (fields
        (field (name "PART NUMBER") "1-2176092-8")
        (field (name "MANUFACTURER") "TE Connectivity Passive Product")
      )
      (libsource (lib "Celestial Altium Library - altium_library") (part "Resistor"))
    )
    (comp (ref "R39")
      (value "18 kOhms")
      (footprint "RES 0805_2012")
      (description "RES SMD 1K OHM 0.1% 1/4W 0805")
      (fields
        (field (name "PART NUMBER") "1-2176092-8")
        (field (name "MANUFACTURER") "TE Connectivity Passive Product")
      )
      (libsource (lib "Celestial Altium Library - altium_library") (part "Resistor"))
    )
    (comp (ref "R40")
      (value "10 kOhms")
      (footprint "RES 0805_2012")
      (description "RES SMD 1K OHM 0.1% 1/4W 0805")
      (fields
        (field (name "PART NUMBER") "1-2176092-8")
        (field (name "MANUFACTURER") "TE Connectivity Passive Product")
      )
      (libsource (lib "Celestial Altium Library - altium_library") (part "Resistor"))
    )
    (comp (ref "R41")
      (value "1.13 MOhms")
      (footprint "RES 0805_2012")
      (description "RES SMD 1K OHM 0.1% 1/4W 0805")
      (fields
        (field (name "PART NUMBER") "1-2176092-8")
        (field (name "MANUFACTURER") "TE Connectivity Passive Product")
      )
      (libsource (lib "Celestial Altium Library - altium_library") (part "Resistor"))
    )
    (comp (ref "R42")
      (value "10 kOhms")
      (footprint "RES 0805_2012")
      (description "RES SMD 1K OHM 0.1% 1/4W 0805")
      (fields
        (field (name "PART NUMBER") "1-2176092-8")
        (field (name "MANUFACTURER") "TE Connectivity Passive Product")
      )
      (libsource (lib "Celestial Altium Library - altium_library") (part "Resistor"))
    )
    (comp (ref "R43")
      (value "100 kOhms")
      (footprint "RES 0805_2012")
      (description "RES SMD 1K OHM 0.1% 1/4W 0805")
      (fields
        (field (name "PART NUMBER") "1-2176092-8")
        (field (name "MANUFACTURER") "TE Connectivity Passive Product")
      )
      (libsource (lib "Celestial Altium Library - altium_library") (part "Resistor"))
    )
    (comp (ref "R44")
      (value "400 kOhms")
      (footprint "RES 0805_2012")
      (description "RES SMD 1K OHM 0.1% 1/4W 0805")
      (fields
        (field (name "PART NUMBER") "1-2176092-8")
        (field (name "MANUFACTURER") "TE Connectivity Passive Product")
      )
      (libsource (lib "Celestial Altium Library - altium_library") (part "Resistor"))
    )
    (comp (ref "R45")
      (value "250 kOhms")
      (footprint "RES 0805_2012")
      (description "RES SMD 1K OHM 0.1% 1/4W 0805")
      (fields
        (field (name "PART NUMBER") "1-2176092-8")
        (field (name "MANUFACTURER") "TE Connectivity Passive Product")
      )
      (libsource (lib "Celestial Altium Library - altium_library") (part "Resistor"))
    )
    (comp (ref "R46")
      (value "5 kOhms")
      (footprint "RES 0805_2012")
      (description "RES SMD 1K OHM 0.1% 1/4W 0805")
      (fields
        (field (name "PART NUMBER") "1-2176092-8")
        (field (name "MANUFACTURER") "TE Connectivity Passive Product")
      )
      (libsource (lib "Celestial Altium Library - altium_library") (part "Resistor"))
    )
    (comp (ref "R47")
      (value "1.13 MOhms")
      (footprint "RES 0805_2012")
      (description "RES SMD 1K OHM 0.1% 1/4W 0805")
      (fields
        (field (name "PART NUMBER") "1-2176092-8")
        (field (name "MANUFACTURER") "TE Connectivity Passive Product")
      )
      (libsource (lib "Celestial Altium Library - altium_library") (part "Resistor"))
    )
    (comp (ref "R48")
      (value "10 kOhms")
      (footprint "RES 0805_2012")
      (description "RES SMD 1K OHM 0.1% 1/4W 0805")
      (fields
        (field (name "PART NUMBER") "1-2176092-8")
        (field (name "MANUFACTURER") "TE Connectivity Passive Product")
      )
      (libsource (lib "Celestial Altium Library - altium_library") (part "Resistor"))
    )
    (comp (ref "R49")
      (value "18 kOhms")
      (footprint "RES 0805_2012")
      (description "RES SMD 1K OHM 0.1% 1/4W 0805")
      (fields
        (field (name "PART NUMBER") "1-2176092-8")
        (field (name "MANUFACTURER") "TE Connectivity Passive Product")
      )
      (libsource (lib "Celestial Altium Library - altium_library") (part "Resistor"))
    )
    (comp (ref "R50")
      (value "10 kOhms")
      (footprint "RES 0805_2012")
      (description "RES SMD 1K OHM 0.1% 1/4W 0805")
      (fields
        (field (name "PART NUMBER") "1-2176092-8")
        (field (name "MANUFACTURER") "TE Connectivity Passive Product")
      )
      (libsource (lib "Celestial Altium Library - altium_library") (part "Resistor"))
    )
    (comp (ref "R51")
      (value "18 kOhms")
      (footprint "RES 0805_2012")
      (description "RES SMD 1K OHM 0.1% 1/4W 0805")
      (fields
        (field (name "PART NUMBER") "1-2176092-8")
        (field (name "MANUFACTURER") "TE Connectivity Passive Product")
      )
      (libsource (lib "Celestial Altium Library - altium_library") (part "Resistor"))
    )
    (comp (ref "Rfbt1")
      (value "100 kOhms")
      (footprint "RES 0805_2012")
      (description "RES SMD 1K OHM 0.1% 1/4W 0805")
      (fields
        (field (name "PART NUMBER") "1-2176092-8")
        (field (name "MANUFACTURER") "TE Connectivity Passive Product")
      )
      (libsource (lib "Celestial Altium Library - altium_library") (part "Resistor"))
    )
    (comp (ref "Rfreq1")
      (value "78.7kOhms")
      (footprint "RES 0805_2012")
      (description "RES SMD 1K OHM 0.1% 1/4W 0805")
      (fields
        (field (name "PART NUMBER") "1-2176092-8")
        (field (name "MANUFACTURER") "TE Connectivity Passive Product")
      )
      (libsource (lib "Celestial Altium Library - altium_library") (part "Resistor"))
    )
    (comp (ref "Rfreq2")
      (value "78.7kOhms")
      (footprint "RES 0805_2012")
      (description "RES SMD 1K OHM 0.1% 1/4W 0805")
      (fields
        (field (name "PART NUMBER") "1-2176092-8")
        (field (name "MANUFACTURER") "TE Connectivity Passive Product")
      )
      (libsource (lib "Celestial Altium Library - altium_library") (part "Resistor"))
    )
    (comp (ref "RPGOOD1")
      (value "100 kOhms")
      (footprint "RES 0805_2012")
      (description "RES SMD 1K OHM 0.1% 1/4W 0805")
      (fields
        (field (name "PART NUMBER") "1-2176092-8")
        (field (name "MANUFACTURER") "TE Connectivity Passive Product")
      )
      (libsource (lib "Celestial Altium Library - altium_library") (part "Resistor"))
    )
    (comp (ref "RPGOOD2")
      (value "100 kOhms")
      (footprint "RES 0805_2012")
      (description "RES SMD 1K OHM 0.1% 1/4W 0805")
      (fields
        (field (name "PART NUMBER") "1-2176092-8")
        (field (name "MANUFACTURER") "TE Connectivity Passive Product")
      )
      (libsource (lib "Celestial Altium Library - altium_library") (part "Resistor"))
    )
    (comp (ref "U1")
      (value "OPA4140AIPWR")
      (footprint "PW0014A_L")
      (fields (field (name "MANUFACTURER") "Texas Instruments"))
      (libsource (lib "Altium Content Vault") (part "TI-OPA16X4_4XXX-14"))
    )
    (comp (ref "U2")
      (value "LM73606QRNPTQ1")
      (footprint "FP-RNP0030A-IPC_C")
      (description "IC REG BUCK ADJUSTABLE 6A 30WQFN")
      (fields
        (field (name "OCTOPART") "https://octopart.com/lm73606qrnptq1-texas+instruments-87960447")
        (field (name "MANUFACTURER") "Texas Instruments")
      )
      (libsource (lib "Components - 06.07.23 - 15.31") (part "CMP-04918-000121-1"))
    )
    (comp (ref "U3")
      (value "LM73606QRNPTQ1")
      (footprint "FP-RNP0030A-IPC_C")
      (description "IC REG BUCK ADJUSTABLE 6A 30WQFN")
      (fields
        (field (name "OCTOPART") "https://octopart.com/lm73606qrnptq1-texas+instruments-87960447")
        (field (name "MANUFACTURER") "Texas Instruments")
      )
      (libsource (lib "Components - 06.07.23 - 15.31") (part "CMP-04918-000121-1"))
    )
    (comp (ref "U4")
      (value "OPA4140AIPWR")
      (footprint "PW0014A_L")
      (fields (field (name "MANUFACTURER") "Texas Instruments"))
      (libsource (lib "Altium Content Vault") (part "TI-OPA16X4_4XXX-14"))
    )
    (comp (ref "U5")
      (value "TLV9034QPWRQ1")
      (footprint "TSOP65P640X120-14N")
      (description "Comparator Push pull output")
      (libsource (lib "UW_SSEC") (part "TLV9034PWRQ1"))
    )
    (comp (ref "U6")
      (value "TLV9024PWRQ1")
      (footprint "TSOP65P640X120-14N")
      (description "Comparator quad")
      (libsource (lib "UW_SSEC") (part "TLV9024PWRQ1"))
    )
    (comp (ref "U7")
      (value "SN74HC00QDRQ1")
      (footprint "D0014A_L")
      (description "Automotive Catalog Quad 2-Input Positive-NAND Gates, D0014A, LARGE T&R")
      (fields
        (field (name "MANUFACTURER") "Texas Instruments")
        (field (name "GENERIC PART NUMBER") "SN74HC00-Q1")
      )
      (libsource (lib "NANDfinal- 01.08.23 - 10.57") (part "CMP-1627-00175-2"))
    )
  )
  (nets
    (net (code "1") (name "/D_gnd") (class "Default")
      (node (ref "C16") (pin "2") (pinfunction "2_2") (pintype "passive"))
      (node (ref "IC2") (pin "2") (pinfunction "GND1_1_2") (pintype "passive"))
      (node (ref "IC2") (pin "8") (pinfunction "GND1_2_8") (pintype "passive"))
      (node (ref "J3") (pin "2") (pinfunction "2_2") (pintype "passive"))
    )
    (net (code "2") (name "/EN (IN)") (class "Default")
      (node (ref "IC2") (pin "3") (pinfunction "INA_3") (pintype "passive"))
      (node (ref "J3") (pin "4") (pinfunction "4_4") (pintype "passive"))
    )
    (net (code "3") (name "/Output") (class "Default")
      (node (ref "J1") (pin "1") (pinfunction "1_1") (pintype "passive"))
      (node (ref "R16") (pin "2") (pinfunction "2_2") (pintype "passive"))
      (node (ref "R32") (pin "2") (pinfunction "2_2") (pintype "passive"))
    )
    (net (code "4") (name "/PGOOD (OUT)") (class "Default")
      (node (ref "IC2") (pin "6") (pinfunction "OUTD_6") (pintype "passive"))
      (node (ref "J3") (pin "3") (pinfunction "3_3") (pintype "passive"))
    )
    (net (code "5") (name "/Reset (IN)") (class "Default")
      (node (ref "IC2") (pin "5") (pinfunction "INC_5") (pintype "passive"))
      (node (ref "J3") (pin "6") (pinfunction "6_6") (pintype "passive"))
    )
    (net (code "6") (name "/Setpoint") (class "Default")
      (node (ref "IC2") (pin "13") (pinfunction "OUTB_13") (pintype "passive"))
      (node (ref "R38") (pin "1") (pinfunction "1_1") (pintype "passive"))
    )
    (net (code "7") (name "/Setpoint (IN)") (class "Default")
      (node (ref "IC2") (pin "4") (pinfunction "INB_4") (pintype "passive"))
      (node (ref "J3") (pin "5") (pinfunction "5_5") (pintype "passive"))
    )
    (net (code "8") (name "/VOPA") (class "Default")
      (node (ref "C13") (pin "2") (pinfunction "2_2") (pintype "passive"))
      (node (ref "C3") (pin "2") (pinfunction "2_2") (pintype "passive"))
      (node (ref "R15") (pin "1") (pinfunction "1_1") (pintype "passive"))
      (node (ref "U1") (pin "4") (pinfunction "V+_4") (pintype "power_in"))
      (node (ref "U4") (pin "4") (pinfunction "V+_4") (pintype "power_in"))
    )
    (net (code "9") (name "/Vcc1") (class "Default")
      (node (ref "C16") (pin "1") (pinfunction "1_1") (pintype "passive"))
      (node (ref "IC2") (pin "1") (pinfunction "VCC1_1") (pintype "passive"))
      (node (ref "IC2") (pin "7") (pinfunction "EN1_7") (pintype "passive"))
      (node (ref "J3") (pin "1") (pinfunction "1_1") (pintype "passive"))
    )
    (net (code "10") (name "/Vcc2") (class "Default")
      (node (ref "C1") (pin "1") (pinfunction "1_1") (pintype "passive"))
      (node (ref "C15") (pin "2") (pinfunction "2_2") (pintype "passive"))
      (node (ref "C19") (pin "1") (pinfunction "1_1") (pintype "passive"))
      (node (ref "C20") (pin "2") (pinfunction "2_2") (pintype "passive"))
      (node (ref "C21") (pin "2") (pinfunction "2_2") (pintype "passive"))
      (node (ref "Cbias1") (pin "2") (pinfunction "2_2") (pintype "passive"))
      (node (ref "Cff1") (pin "2") (pinfunction "2_2") (pintype "passive"))
      (node (ref "Cout1") (pin "1") (pinfunction "1_1") (pintype "passive"))
      (node (ref "Cout2") (pin "2") (pinfunction "2_2") (pintype "passive"))
      (node (ref "IC1") (pin "4") (pinfunction "VIN_4") (pintype "passive"))
      (node (ref "IC2") (pin "10") (pinfunction "EN2_10") (pintype "passive"))
      (node (ref "IC2") (pin "16") (pinfunction "VCC2_16") (pintype "passive"))
      (node (ref "L2") (pin "2") (pinfunction "2_2") (pintype "passive"))
      (node (ref "R43") (pin "1") (pinfunction "1_1") (pintype "passive"))
      (node (ref "R46") (pin "1") (pinfunction "1_1") (pintype "passive"))
      (node (ref "R47") (pin "1") (pinfunction "1_1") (pintype "passive"))
      (node (ref "R50") (pin "1") (pinfunction "1_1") (pintype "passive"))
      (node (ref "R51") (pin "1") (pinfunction "1_1") (pintype "passive"))
      (node (ref "RPGOOD1") (pin "2") (pinfunction "2_2") (pintype "passive"))
      (node (ref "RPGOOD2") (pin "2") (pinfunction "2_2") (pintype "passive"))
      (node (ref "Rfbt1") (pin "2") (pinfunction "2_2") (pintype "passive"))
      (node (ref "U5") (pin "3") (pinfunction "V+_3") (pintype "passive"))
      (node (ref "U6") (pin "3") (pinfunction "V+_3") (pintype "passive"))
      (node (ref "U7") (pin "14") (pinfunction "VCC_14") (pintype "power_in"))
    )
    (net (code "11") (name "/Vin") (class "Default")
      (node (ref "CBulk1") (pin "1") (pinfunction "1_1") (pintype "passive"))
      (node (ref "CBulk2") (pin "1") (pinfunction "1_1") (pintype "passive"))
      (node (ref "Cin1") (pin "1") (pinfunction "1_1") (pintype "passive"))
      (node (ref "Cin2") (pin "1") (pinfunction "1_1") (pintype "passive"))
      (node (ref "Cin3") (pin "1") (pinfunction "1_1") (pintype "passive"))
      (node (ref "Cin4") (pin "1") (pinfunction "1_1") (pintype "passive"))
      (node (ref "J2") (pin "2") (pinfunction "2_2") (pintype "passive"))
      (node (ref "R1") (pin "1") (pinfunction "1_1") (pintype "passive"))
      (node (ref "R2") (pin "1") (pinfunction "1_1") (pintype "passive"))
      (node (ref "R3") (pin "2") (pinfunction "2_2") (pintype "passive"))
      (node (ref "R4") (pin "2") (pinfunction "2_2") (pintype "passive"))
      (node (ref "R5") (pin "2") (pinfunction "2_2") (pintype "passive"))
      (node (ref "R6") (pin "2") (pinfunction "2_2") (pintype "passive"))
      (node (ref "U2") (pin "18") (pinfunction "EN_18") (pintype "input"))
      (node (ref "U2") (pin "20") (pinfunction "PVIN_20") (pintype "power_in"))
      (node (ref "U2") (pin "21") (pinfunction "PVIN_21") (pintype "power_in"))
      (node (ref "U2") (pin "22") (pinfunction "PVIN_22") (pintype "power_in"))
      (node (ref "U3") (pin "20") (pinfunction "PVIN_20") (pintype "power_in"))
      (node (ref "U3") (pin "21") (pinfunction "PVIN_21") (pintype "power_in"))
      (node (ref "U3") (pin "22") (pinfunction "PVIN_22") (pintype "power_in"))
    )
    (net (code "12") (name "/Vref") (class "Default")
      (node (ref "R19") (pin "2") (pinfunction "2_2") (pintype "passive"))
      (node (ref "R21") (pin "2") (pinfunction "2_2") (pintype "passive"))
      (node (ref "R22") (pin "2") (pinfunction "2_2") (pintype "passive"))
      (node (ref "U4") (pin "6") (pinfunction "IN_B-_6") (pintype "input"))
      (node (ref "U4") (pin "7") (pinfunction "OUT_B_7") (pintype "output"))
    )
    (net (code "13") (name "/Vsense_b") (class "Default")
      (node (ref "C14") (pin "2") (pinfunction "2_2") (pintype "passive"))
      (node (ref "R31") (pin "2") (pinfunction "2_2") (pintype "passive"))
      (node (ref "R34") (pin "2") (pinfunction "2_2") (pintype "passive"))
      (node (ref "U4") (pin "1") (pinfunction "OUT_A_1") (pintype "output"))
      (node (ref "U5") (pin "6") (pinfunction "IN2-_6") (pintype "input"))
    )
    (net (code "14") (name "/Vsp") (class "Default")
      (node (ref "C18") (pin "2") (pinfunction "2_2") (pintype "passive"))
      (node (ref "R20") (pin "2") (pinfunction "2_2") (pintype "passive"))
      (node (ref "R24") (pin "2") (pinfunction "2_2") (pintype "passive"))
      (node (ref "R39") (pin "2") (pinfunction "2_2") (pintype "passive"))
    )
    (net (code "15") (name "GND") (class "Default")
      (node (ref "C1") (pin "2") (pinfunction "2_2") (pintype "passive"))
      (node (ref "C13") (pin "1") (pinfunction "1_1") (pintype "passive"))
      (node (ref "C15") (pin "1") (pinfunction "1_1") (pintype "passive"))
      (node (ref "C17") (pin "1") (pinfunction "1_1") (pintype "passive"))
      (node (ref "C18") (pin "1") (pinfunction "1_1") (pintype "passive"))
      (node (ref "C19") (pin "2") (pinfunction "2_2") (pintype "passive"))
      (node (ref "C2") (pin "1") (pinfunction "1_1") (pintype "passive"))
      (node (ref "C20") (pin "1") (pinfunction "1_1") (pintype "passive"))
      (node (ref "C21") (pin "1") (pinfunction "1_1") (pintype "passive"))
      (node (ref "C3") (pin "1") (pinfunction "1_1") (pintype "passive"))
      (node (ref "CBulk1") (pin "2") (pinfunction "2_2") (pintype "passive"))
      (node (ref "CBulk2") (pin "2") (pinfunction "2_2") (pintype "passive"))
      (node (ref "CVcc1") (pin "2") (pinfunction "2_2") (pintype "passive"))
      (node (ref "CVcc2") (pin "2") (pinfunction "2_2") (pintype "passive"))
      (node (ref "Cbias1") (pin "1") (pinfunction "1_1") (pintype "passive"))
      (node (ref "Cin1") (pin "2") (pinfunction "2_2") (pintype "passive"))
      (node (ref "Cin2") (pin "2") (pinfunction "2_2") (pintype "passive"))
      (node (ref "Cin3") (pin "2") (pinfunction "2_2") (pintype "passive"))
      (node (ref "Cin4") (pin "2") (pinfunction "2_2") (pintype "passive"))
      (node (ref "Cout1") (pin "2") (pinfunction "2_2") (pintype "passive"))
      (node (ref "Cout2") (pin "1") (pinfunction "1_1") (pintype "passive"))
      (node (ref "Cout3") (pin "2") (pinfunction "2_2") (pintype "passive"))
      (node (ref "Cout4") (pin "1") (pinfunction "1_1") (pintype "passive"))
      (node (ref "IC1") (pin "1") (pinfunction "GND_1_1") (pintype "passive"))
      (node (ref "IC1") (pin "2") (pinfunction "GND_2_2") (pintype "passive"))
      (node (ref "IC1") (pin "3") (pinfunction "NC_1_3") (pintype "passive"))
      (node (ref "IC1") (pin "5") (pinfunction "NC_2_5") (pintype "passive"))
      (node (ref "IC2") (pin "15") (pinfunction "GND2_2_15") (pintype "passive"))
      (node (ref "IC2") (pin "9") (pinfunction "GND2_1_9") (pintype "passive"))
      (node (ref "J1") (pin "2") (pinfunction "2_2") (pintype "passive"))
      (node (ref "J2") (pin "1") (pinfunction "1_1") (pintype "passive"))
      (node (ref "Q3") (pin "2") (pinfunction "E_2") (pintype "passive"))
      (node (ref "R10") (pin "1") (pinfunction "1_1") (pintype "passive"))
      (node (ref "R14") (pin "2") (pinfunction "2_2") (pintype "passive"))
      (node (ref "R18") (pin "1") (pinfunction "1_1") (pintype "passive"))
      (node (ref "R23") (pin "1") (pinfunction "1_1") (pintype "passive"))
      (node (ref "R30") (pin "2") (pinfunction "2_2") (pintype "passive"))
      (node (ref "R41") (pin "2") (pinfunction "2_2") (pintype "passive"))
      (node (ref "R44") (pin "1") (pinfunction "1_1") (pintype "passive"))
      (node (ref "R48") (pin "2") (pinfunction "2_2") (pintype "passive"))
      (node (ref "R49") (pin "2") (pinfunction "2_2") (pintype "passive"))
      (node (ref "Rfreq1") (pin "1") (pinfunction "1_1") (pintype "passive"))
      (node (ref "Rfreq2") (pin "1") (pinfunction "1_1") (pintype "passive"))
      (node (ref "U1") (pin "11") (pinfunction "V-_11") (pintype "power_in"))
      (node (ref "U2") (pin "12") (pinfunction "NC_12") (pintype "passive"))
      (node (ref "U2") (pin "13") (pinfunction "NC_13") (pintype "passive"))
      (node (ref "U2") (pin "14") (pinfunction "NC_14") (pintype "passive"))
      (node (ref "U2") (pin "15") (pinfunction "NC_15") (pintype "passive"))
      (node (ref "U2") (pin "17") (pinfunction "SYNC/MODE_17") (pintype "input"))
      (node (ref "U2") (pin "19") (pinfunction "AGND_19") (pintype "power_in"))
      (node (ref "U2") (pin "23") (pinfunction "PGND_23") (pintype "power_in"))
      (node (ref "U2") (pin "24") (pinfunction "PGND_24") (pintype "power_in"))
      (node (ref "U2") (pin "25") (pinfunction "PGND_25") (pintype "power_in"))
      (node (ref "U2") (pin "26") (pinfunction "PGND_26") (pintype "power_in"))
      (node (ref "U2") (pin "27") (pinfunction "NC_27") (pintype "passive"))
      (node (ref "U2") (pin "28") (pinfunction "NC_28") (pintype "passive"))
      (node (ref "U2") (pin "29") (pinfunction "NC_29") (pintype "passive"))
      (node (ref "U2") (pin "30") (pinfunction "NC_30") (pintype "passive"))
      (node (ref "U2") (pin "31") (pinfunction "DAP_31") (pintype "power_in"))
      (node (ref "U2") (pin "8") (pinfunction "BIAS_8") (pintype "power_in"))
      (node (ref "U3") (pin "12") (pinfunction "NC_12") (pintype "passive"))
      (node (ref "U3") (pin "13") (pinfunction "NC_13") (pintype "passive"))
      (node (ref "U3") (pin "14") (pinfunction "NC_14") (pintype "passive"))
      (node (ref "U3") (pin "15") (pinfunction "NC_15") (pintype "passive"))
      (node (ref "U3") (pin "17") (pinfunction "SYNC/MODE_17") (pintype "input"))
      (node (ref "U3") (pin "19") (pinfunction "AGND_19") (pintype "power_in"))
      (node (ref "U3") (pin "23") (pinfunction "PGND_23") (pintype "power_in"))
      (node (ref "U3") (pin "24") (pinfunction "PGND_24") (pintype "power_in"))
      (node (ref "U3") (pin "25") (pinfunction "PGND_25") (pintype "power_in"))
      (node (ref "U3") (pin "26") (pinfunction "PGND_26") (pintype "power_in"))
      (node (ref "U3") (pin "27") (pinfunction "NC_27") (pintype "passive"))
      (node (ref "U3") (pin "28") (pinfunction "NC_28") (pintype "passive"))
      (node (ref "U3") (pin "29") (pinfunction "NC_29") (pintype "passive"))
      (node (ref "U3") (pin "30") (pinfunction "NC_30") (pintype "passive"))
      (node (ref "U3") (pin "31") (pinfunction "DAP_31") (pintype "power_in"))
      (node (ref "U3") (pin "8") (pinfunction "BIAS_8") (pintype "power_in"))
      (node (ref "U4") (pin "11") (pinfunction "V-_11") (pintype "power_in"))
      (node (ref "U5") (pin "12") (pinfunction "V-_12") (pintype "passive"))
      (node (ref "U6") (pin "12") (pinfunction "V-_12") (pintype "passive"))
      (node (ref "U7") (pin "7") (pinfunction "GND_7") (pintype "power_in"))
    )
    (net (code "16") (name "Net-(C17-Pad2)") (class "Default")
      (node (ref "C17") (pin "2") (pinfunction "2_2") (pintype "passive"))
      (node (ref "R38") (pin "2") (pinfunction "2_2") (pintype "passive"))
      (node (ref "R39") (pin "1") (pinfunction "1_1") (pintype "passive"))
    )
    (net (code "17") (name "Net-(CBOOT1-Pad1)") (class "Default")
      (node (ref "CBOOT1") (pin "1") (pinfunction "1_1") (pintype "passive"))
      (node (ref "L2") (pin "1") (pinfunction "1_1") (pintype "passive"))
      (node (ref "U2") (pin "1") (pinfunction "SW_1") (pintype "passive"))
      (node (ref "U2") (pin "2") (pinfunction "SW_2") (pintype "passive"))
      (node (ref "U2") (pin "3") (pinfunction "SW_3") (pintype "passive"))
      (node (ref "U2") (pin "4") (pinfunction "SW_4") (pintype "passive"))
      (node (ref "U2") (pin "5") (pinfunction "SW_5") (pintype "passive"))
    )
    (net (code "18") (name "Net-(CBOOT2-Pad1)") (class "Default")
      (node (ref "CBOOT2") (pin "1") (pinfunction "1_1") (pintype "passive"))
      (node (ref "L3") (pin "1") (pinfunction "1_1") (pintype "passive"))
      (node (ref "U3") (pin "1") (pinfunction "SW_1") (pintype "passive"))
      (node (ref "U3") (pin "2") (pinfunction "SW_2") (pintype "passive"))
      (node (ref "U3") (pin "3") (pinfunction "SW_3") (pintype "passive"))
      (node (ref "U3") (pin "4") (pinfunction "SW_4") (pintype "passive"))
      (node (ref "U3") (pin "5") (pinfunction "SW_5") (pintype "passive"))
    )
    (net (code "19") (name "Net-(Cff2-Pad2)") (class "Default")
      (node (ref "Cff2") (pin "2") (pinfunction "2_2") (pintype "passive"))
      (node (ref "Cout3") (pin "1") (pinfunction "1_1") (pintype "passive"))
      (node (ref "Cout4") (pin "2") (pinfunction "2_2") (pintype "passive"))
      (node (ref "L3") (pin "2") (pinfunction "2_2") (pintype "passive"))
      (node (ref "R17") (pin "2") (pinfunction "2_2") (pintype "passive"))
    )
    (net (code "20") (name "Net-(IC1-VOUT)") (class "Default")
      (node (ref "C2") (pin "2") (pinfunction "2_2") (pintype "passive"))
      (node (ref "IC1") (pin "6") (pinfunction "VOUT_6") (pintype "passive"))
      (node (ref "U4") (pin "5") (pinfunction "IN_B+_5") (pintype "input"))
    )
    (net (code "21") (name "Net-(IC2-IND)") (class "Default")
      (node (ref "IC2") (pin "11") (pinfunction "IND_11") (pintype "passive"))
      (node (ref "U5") (pin "1") (pinfunction "OUT2_1") (pintype "output"))
    )
    (net (code "22") (name "Net-(IC2-OUTA)") (class "Default")
      (node (ref "IC2") (pin "14") (pinfunction "OUTA_14") (pintype "passive"))
      (node (ref "U7") (pin "9") (pinfunction "3A_9") (pintype "input"))
    )
    (net (code "23") (name "Net-(IC2-OUTC)") (class "Default")
      (node (ref "IC2") (pin "12") (pinfunction "OUTC_12") (pintype "passive"))
      (node (ref "R48") (pin "1") (pinfunction "1_1") (pintype "passive"))
      (node (ref "U7") (pin "5") (pinfunction "2B_5") (pintype "input"))
    )
    (net (code "24") (name "Net-(Q1-B)") (class "Default")
      (node (ref "Q1") (pin "1") (pinfunction "B_1") (pintype "passive"))
      (node (ref "R7") (pin "1") (pinfunction "1_1") (pintype "passive"))
    )
    (net (code "25") (name "Net-(Q1-C)") (class "Default")
      (node (ref "C4") (pin "2") (pinfunction "2_2") (pintype "passive"))
      (node (ref "C5") (pin "2") (pinfunction "2_2") (pintype "passive"))
      (node (ref "C6") (pin "2") (pinfunction "2_2") (pintype "passive"))
      (node (ref "Q1") (pin "3") (pinfunction "C_3") (pintype "passive"))
      (node (ref "Q2") (pin "2") (pinfunction "C_2") (pintype "passive"))
      (node (ref "Q2") (pin "4") (pinfunction "C_4") (pintype "passive"))
    )
    (net (code "26") (name "Net-(Q1-E)") (class "Default")
      (node (ref "Q1") (pin "2") (pinfunction "E_2") (pintype "passive"))
      (node (ref "Q4") (pin "2") (pinfunction "C_2") (pintype "passive"))
      (node (ref "Q4") (pin "4") (pinfunction "C_4") (pintype "passive"))
      (node (ref "R15") (pin "2") (pinfunction "2_2") (pintype "passive"))
    )
    (net (code "27") (name "Net-(Q2-B)") (class "Default")
      (node (ref "Q2") (pin "1") (pinfunction "B_1") (pintype "passive"))
      (node (ref "R8") (pin "1") (pinfunction "1_1") (pintype "passive"))
    )
    (net (code "28") (name "Net-(Q2-E)") (class "Default")
      (node (ref "Q2") (pin "3") (pinfunction "E_3") (pintype "passive"))
      (node (ref "R1") (pin "2") (pinfunction "2_2") (pintype "passive"))
    )
    (net (code "29") (name "Net-(Q3-B)") (class "Default")
      (node (ref "Q3") (pin "1") (pinfunction "B_1") (pintype "passive"))
      (node (ref "R13") (pin "2") (pinfunction "2_2") (pintype "passive"))
    )
    (net (code "30") (name "Net-(Q3-C)") (class "Default")
      (node (ref "C4") (pin "1") (pinfunction "1_1") (pintype "passive"))
      (node (ref "C5") (pin "1") (pinfunction "1_1") (pintype "passive"))
      (node (ref "C6") (pin "1") (pinfunction "1_1") (pintype "passive"))
      (node (ref "Q3") (pin "3") (pinfunction "C_3") (pintype "passive"))
      (node (ref "Q4") (pin "3") (pinfunction "E_3") (pintype "passive"))
    )
    (net (code "31") (name "Net-(Q4-B)") (class "Default")
      (node (ref "Q4") (pin "1") (pinfunction "B_1") (pintype "passive"))
      (node (ref "R12") (pin "2") (pinfunction "2_2") (pintype "passive"))
    )
    (net (code "32") (name "Net-(Q5-B)") (class "Default")
      (node (ref "C8") (pin "1") (pinfunction "1_1") (pintype "passive"))
      (node (ref "Q5") (pin "1") (pinfunction "B_1") (pintype "passive"))
      (node (ref "R4") (pin "1") (pinfunction "1_1") (pintype "passive"))
    )
    (net (code "33") (name "Net-(Q5-C)") (class "Default")
      (node (ref "C7") (pin "1") (pinfunction "1_1") (pintype "passive"))
      (node (ref "Q5") (pin "3") (pinfunction "C_3") (pintype "passive"))
      (node (ref "R3") (pin "1") (pinfunction "1_1") (pintype "passive"))
    )
    (net (code "34") (name "Net-(Q5-E)") (class "Default")
      (node (ref "Q5") (pin "2") (pinfunction "E_2") (pintype "passive"))
      (node (ref "Q6") (pin "2") (pinfunction "E_2") (pintype "passive"))
    )
    (net (code "35") (name "Net-(Q6-B)") (class "Default")
      (node (ref "C7") (pin "2") (pinfunction "2_2") (pintype "passive"))
      (node (ref "Q6") (pin "1") (pinfunction "B_1") (pintype "passive"))
      (node (ref "R5") (pin "1") (pinfunction "1_1") (pintype "passive"))
    )
    (net (code "36") (name "Net-(Q6-C)") (class "Default")
      (node (ref "C8") (pin "2") (pinfunction "2_2") (pintype "passive"))
      (node (ref "Q6") (pin "3") (pinfunction "C_3") (pintype "passive"))
      (node (ref "R11") (pin "1") (pinfunction "1_1") (pintype "passive"))
      (node (ref "R13") (pin "1") (pinfunction "1_1") (pintype "passive"))
      (node (ref "R6") (pin "1") (pinfunction "1_1") (pintype "passive"))
      (node (ref "R8") (pin "2") (pinfunction "2_2") (pintype "passive"))
      (node (ref "R9") (pin "2") (pinfunction "2_2") (pintype "passive"))
    )
    (net (code "37") (name "Net-(R2-Pad2)") (class "Default")
      (node (ref "R2") (pin "2") (pinfunction "2_2") (pintype "passive"))
      (node (ref "R7") (pin "2") (pinfunction "2_2") (pintype "passive"))
      (node (ref "R9") (pin "1") (pinfunction "1_1") (pintype "passive"))
    )
    (net (code "38") (name "Net-(R11-Pad2)") (class "Default")
      (node (ref "R11") (pin "2") (pinfunction "2_2") (pintype "passive"))
      (node (ref "R12") (pin "1") (pinfunction "1_1") (pintype "passive"))
      (node (ref "R14") (pin "1") (pinfunction "1_1") (pintype "passive"))
    )
    (net (code "39") (name "Net-(R16-Pad1)") (class "Default")
      (node (ref "R16") (pin "1") (pinfunction "1_1") (pintype "passive"))
      (node (ref "R29") (pin "2") (pinfunction "2_2") (pintype "passive"))
    )
    (net (code "40") (name "Net-(U1A-IN_A+)") (class "Default")
      (node (ref "R20") (pin "1") (pinfunction "1_1") (pintype "passive"))
      (node (ref "R25") (pin "1") (pinfunction "1_1") (pintype "passive"))
      (node (ref "U1") (pin "3") (pinfunction "IN_A+_3") (pintype "input"))
    )
    (net (code "41") (name "Net-(U1A-IN_A-)") (class "Default")
      (node (ref "R30") (pin "1") (pinfunction "1_1") (pintype "passive"))
      (node (ref "R35") (pin "2") (pinfunction "2_2") (pintype "passive"))
      (node (ref "U1") (pin "2") (pinfunction "IN_A-_2") (pintype "input"))
    )
    (net (code "42") (name "Net-(U1A-OUT_A)") (class "Default")
      (node (ref "R27") (pin "2") (pinfunction "2_2") (pintype "passive"))
      (node (ref "R35") (pin "1") (pinfunction "1_1") (pintype "passive"))
      (node (ref "U1") (pin "1") (pinfunction "OUT_A_1") (pintype "output"))
    )
    (net (code "43") (name "Net-(U1B-IN_B+)") (class "Default")
      (node (ref "R21") (pin "1") (pinfunction "1_1") (pintype "passive"))
      (node (ref "U1") (pin "5") (pinfunction "IN_B+_5") (pintype "input"))
    )
    (net (code "44") (name "Net-(U1B-IN_B-)") (class "Default")
      (node (ref "R26") (pin "1") (pinfunction "1_1") (pintype "passive"))
      (node (ref "R33") (pin "2") (pinfunction "2_2") (pintype "passive"))
      (node (ref "U1") (pin "6") (pinfunction "IN_B-_6") (pintype "input"))
    )
    (net (code "45") (name "Net-(U1B-OUT_B)") (class "Default")
      (node (ref "R25") (pin "2") (pinfunction "2_2") (pintype "passive"))
      (node (ref "R33") (pin "1") (pinfunction "1_1") (pintype "passive"))
      (node (ref "U1") (pin "7") (pinfunction "OUT_B_7") (pintype "output"))
    )
    (net (code "46") (name "Net-(U1C-IN_C+)") (class "Default")
      (node (ref "R22") (pin "1") (pinfunction "1_1") (pintype "passive"))
      (node (ref "U1") (pin "10") (pinfunction "IN_C+_10") (pintype "input"))
    )
    (net (code "47") (name "Net-(U1C-IN_C-)") (class "Default")
      (node (ref "R28") (pin "1") (pinfunction "1_1") (pintype "passive"))
      (node (ref "R36") (pin "2") (pinfunction "2_2") (pintype "passive"))
      (node (ref "U1") (pin "9") (pinfunction "IN_C-_9") (pintype "input"))
    )
    (net (code "48") (name "Net-(U1C-OUT_C)") (class "Default")
      (node (ref "R26") (pin "2") (pinfunction "2_2") (pintype "passive"))
      (node (ref "R36") (pin "1") (pinfunction "1_1") (pintype "passive"))
      (node (ref "U1") (pin "8") (pinfunction "OUT_C_8") (pintype "output"))
    )
    (net (code "49") (name "Net-(U1D-IN_D+)") (class "Default")
      (node (ref "R19") (pin "1") (pinfunction "1_1") (pintype "passive"))
      (node (ref "R24") (pin "1") (pinfunction "1_1") (pintype "passive"))
      (node (ref "U1") (pin "12") (pinfunction "IN_D+_12") (pintype "input"))
    )
    (net (code "50") (name "Net-(U1D-IN_D-)") (class "Default")
      (node (ref "R31") (pin "1") (pinfunction "1_1") (pintype "passive"))
      (node (ref "R37") (pin "2") (pinfunction "2_2") (pintype "passive"))
      (node (ref "U1") (pin "13") (pinfunction "IN_D-_13") (pintype "input"))
    )
    (net (code "51") (name "Net-(U1D-OUT_D)") (class "Default")
      (node (ref "R28") (pin "2") (pinfunction "2_2") (pintype "passive"))
      (node (ref "R37") (pin "1") (pinfunction "1_1") (pintype "passive"))
      (node (ref "U1") (pin "14") (pinfunction "OUT_D_14") (pintype "output"))
      (node (ref "U6") (pin "4") (pinfunction "IN1-_4") (pintype "input"))
      (node (ref "U6") (pin "7") (pinfunction "IN2+_7") (pintype "input"))
    )
    (net (code "52") (name "Net-(U2-CBOOT)") (class "Default")
      (node (ref "CBOOT1") (pin "2") (pinfunction "2_2") (pintype "passive"))
      (node (ref "U2") (pin "6") (pinfunction "CBOOT_6") (pintype "passive"))
    )
    (net (code "53") (name "Net-(U2-FB)") (class "Default")
      (node (ref "Cff1") (pin "1") (pinfunction "1_1") (pintype "passive"))
      (node (ref "R10") (pin "2") (pinfunction "2_2") (pintype "passive"))
      (node (ref "Rfbt1") (pin "1") (pinfunction "1_1") (pintype "passive"))
      (node (ref "U2") (pin "11") (pinfunction "FB_11") (pintype "input"))
    )
    (net (code "54") (name "Net-(U2-PGOOD)") (class "Default")
      (node (ref "RPGOOD1") (pin "1") (pinfunction "1_1") (pintype "passive"))
      (node (ref "U2") (pin "16") (pinfunction "PGOOD_16") (pintype "open_collector"))
    )
    (net (code "55") (name "Net-(U2-RT)") (class "Default")
      (node (ref "Rfreq1") (pin "2") (pinfunction "2_2") (pintype "passive"))
      (node (ref "U2") (pin "9") (pinfunction "RT_9") (pintype "passive"))
    )
    (net (code "56") (name "Net-(U2-VCC)") (class "Default")
      (node (ref "CVcc1") (pin "1") (pinfunction "1_1") (pintype "passive"))
      (node (ref "U2") (pin "7") (pinfunction "VCC_7") (pintype "power_in"))
    )
    (net (code "57") (name "Net-(U3-CBOOT)") (class "Default")
      (node (ref "CBOOT2") (pin "2") (pinfunction "2_2") (pintype "passive"))
      (node (ref "U3") (pin "6") (pinfunction "CBOOT_6") (pintype "passive"))
    )
    (net (code "58") (name "Net-(U3-EN)") (class "Default")
      (node (ref "U3") (pin "18") (pinfunction "EN_18") (pintype "input"))
      (node (ref "U7") (pin "11") (pinfunction "4Y_11") (pintype "output"))
    )
    (net (code "59") (name "Net-(U3-FB)") (class "Default")
      (node (ref "Cff2") (pin "1") (pinfunction "1_1") (pintype "passive"))
      (node (ref "R17") (pin "1") (pinfunction "1_1") (pintype "passive"))
      (node (ref "R18") (pin "2") (pinfunction "2_2") (pintype "passive"))
      (node (ref "R27") (pin "1") (pinfunction "1_1") (pintype "passive"))
      (node (ref "U3") (pin "11") (pinfunction "FB_11") (pintype "input"))
    )
    (net (code "60") (name "Net-(U3-PGOOD)") (class "Default")
      (node (ref "R40") (pin "1") (pinfunction "1_1") (pintype "passive"))
      (node (ref "RPGOOD2") (pin "1") (pinfunction "1_1") (pintype "passive"))
      (node (ref "U3") (pin "16") (pinfunction "PGOOD_16") (pintype "open_collector"))
    )
    (net (code "61") (name "Net-(U3-RT)") (class "Default")
      (node (ref "Rfreq2") (pin "2") (pinfunction "2_2") (pintype "passive"))
      (node (ref "U3") (pin "9") (pinfunction "RT_9") (pintype "passive"))
    )
    (net (code "62") (name "Net-(U3-VCC)") (class "Default")
      (node (ref "CVcc2") (pin "1") (pinfunction "1_1") (pintype "passive"))
      (node (ref "U3") (pin "7") (pinfunction "VCC_7") (pintype "power_in"))
    )
    (net (code "63") (name "Net-(U4A-IN_A+)") (class "Default")
      (node (ref "R23") (pin "2") (pinfunction "2_2") (pintype "passive"))
      (node (ref "R29") (pin "1") (pinfunction "1_1") (pintype "passive"))
      (node (ref "U4") (pin "3") (pinfunction "IN_A+_3") (pintype "input"))
    )
    (net (code "64") (name "Net-(U4A-IN_A-)") (class "Default")
      (node (ref "C14") (pin "1") (pinfunction "1_1") (pintype "passive"))
      (node (ref "R32") (pin "1") (pinfunction "1_1") (pintype "passive"))
      (node (ref "R34") (pin "1") (pinfunction "1_1") (pintype "passive"))
      (node (ref "U4") (pin "2") (pinfunction "IN_A-_2") (pintype "input"))
    )
    (net (code "65") (name "Net-(U5A-IN1+)") (class "Default")
      (node (ref "R40") (pin "2") (pinfunction "2_2") (pintype "passive"))
      (node (ref "R42") (pin "2") (pinfunction "2_2") (pintype "passive"))
      (node (ref "U5") (pin "5") (pinfunction "IN1+_5") (pintype "input"))
    )
    (net (code "66") (name "Net-(U5A-IN1-)") (class "Default")
      (node (ref "R43") (pin "2") (pinfunction "2_2") (pintype "passive"))
      (node (ref "R44") (pin "2") (pinfunction "2_2") (pintype "passive"))
      (node (ref "U5") (pin "4") (pinfunction "IN1-_4") (pintype "input"))
    )
    (net (code "67") (name "Net-(U5B-IN2+)") (class "Default")
      (node (ref "R49") (pin "1") (pinfunction "1_1") (pintype "passive"))
      (node (ref "R51") (pin "2") (pinfunction "2_2") (pintype "passive"))
      (node (ref "U5") (pin "7") (pinfunction "IN2+_7") (pintype "input"))
    )
    (net (code "68") (name "Net-(U5B-OUT1)") (class "Default")
      (node (ref "R50") (pin "2") (pinfunction "2_2") (pintype "passive"))
      (node (ref "U5") (pin "2") (pinfunction "OUT1_2") (pintype "output"))
      (node (ref "U7") (pin "1") (pinfunction "1A_1") (pintype "input"))
    )
    (net (code "69") (name "Net-(U6A-IN1+)") (class "Default")
      (node (ref "R45") (pin "1") (pinfunction "1_1") (pintype "passive"))
      (node (ref "R47") (pin "2") (pinfunction "2_2") (pintype "passive"))
      (node (ref "U6") (pin "5") (pinfunction "IN1+_5") (pintype "input"))
    )
    (net (code "70") (name "Net-(U6A-OUT2)") (class "Default")
      (node (ref "R42") (pin "1") (pinfunction "1_1") (pintype "passive"))
      (node (ref "R46") (pin "2") (pinfunction "2_2") (pintype "passive"))
      (node (ref "U6") (pin "1") (pinfunction "OUT2_1") (pintype "output"))
      (node (ref "U6") (pin "2") (pinfunction "OUT1_2") (pintype "output"))
    )
    (net (code "71") (name "Net-(U6B-IN2-)") (class "Default")
      (node (ref "R41") (pin "1") (pinfunction "1_1") (pintype "passive"))
      (node (ref "R45") (pin "2") (pinfunction "2_2") (pintype "passive"))
      (node (ref "U6") (pin "6") (pinfunction "IN2-_6") (pintype "input"))
    )
    (net (code "72") (name "Net-(U7A-1B)") (class "Default")
      (node (ref "U7") (pin "10") (pinfunction "3B_10") (pintype "input"))
      (node (ref "U7") (pin "2") (pinfunction "1B_2") (pintype "input"))
      (node (ref "U7") (pin "6") (pinfunction "2Y_6") (pintype "output"))
    )
    (net (code "73") (name "Net-(U7A-1Y)") (class "Default")
      (node (ref "U7") (pin "3") (pinfunction "1Y_3") (pintype "output"))
      (node (ref "U7") (pin "4") (pinfunction "2A_4") (pintype "input"))
    )
    (net (code "74") (name "Net-(U7C-3Y)") (class "Default")
      (node (ref "U7") (pin "12") (pinfunction "4A_12") (pintype "input"))
      (node (ref "U7") (pin "13") (pinfunction "4B_13") (pintype "input"))
      (node (ref "U7") (pin "8") (pinfunction "3Y_8") (pintype "output"))
    )
    (net (code "75") (name "unconnected-(U2-SS{slash}TRK-Pad10)") (class "Default")
      (node (ref "U2") (pin "10") (pinfunction "SS/TRK_10") (pintype "passive"))
    )
    (net (code "76") (name "unconnected-(U3-SS{slash}TRK-Pad10)") (class "Default")
      (node (ref "U3") (pin "10") (pinfunction "SS/TRK_10") (pintype "passive"))
    )
  )
)
